# Avalon_ctrlunit.net
KiCad netlist of a schematic drawn in Altium Designer
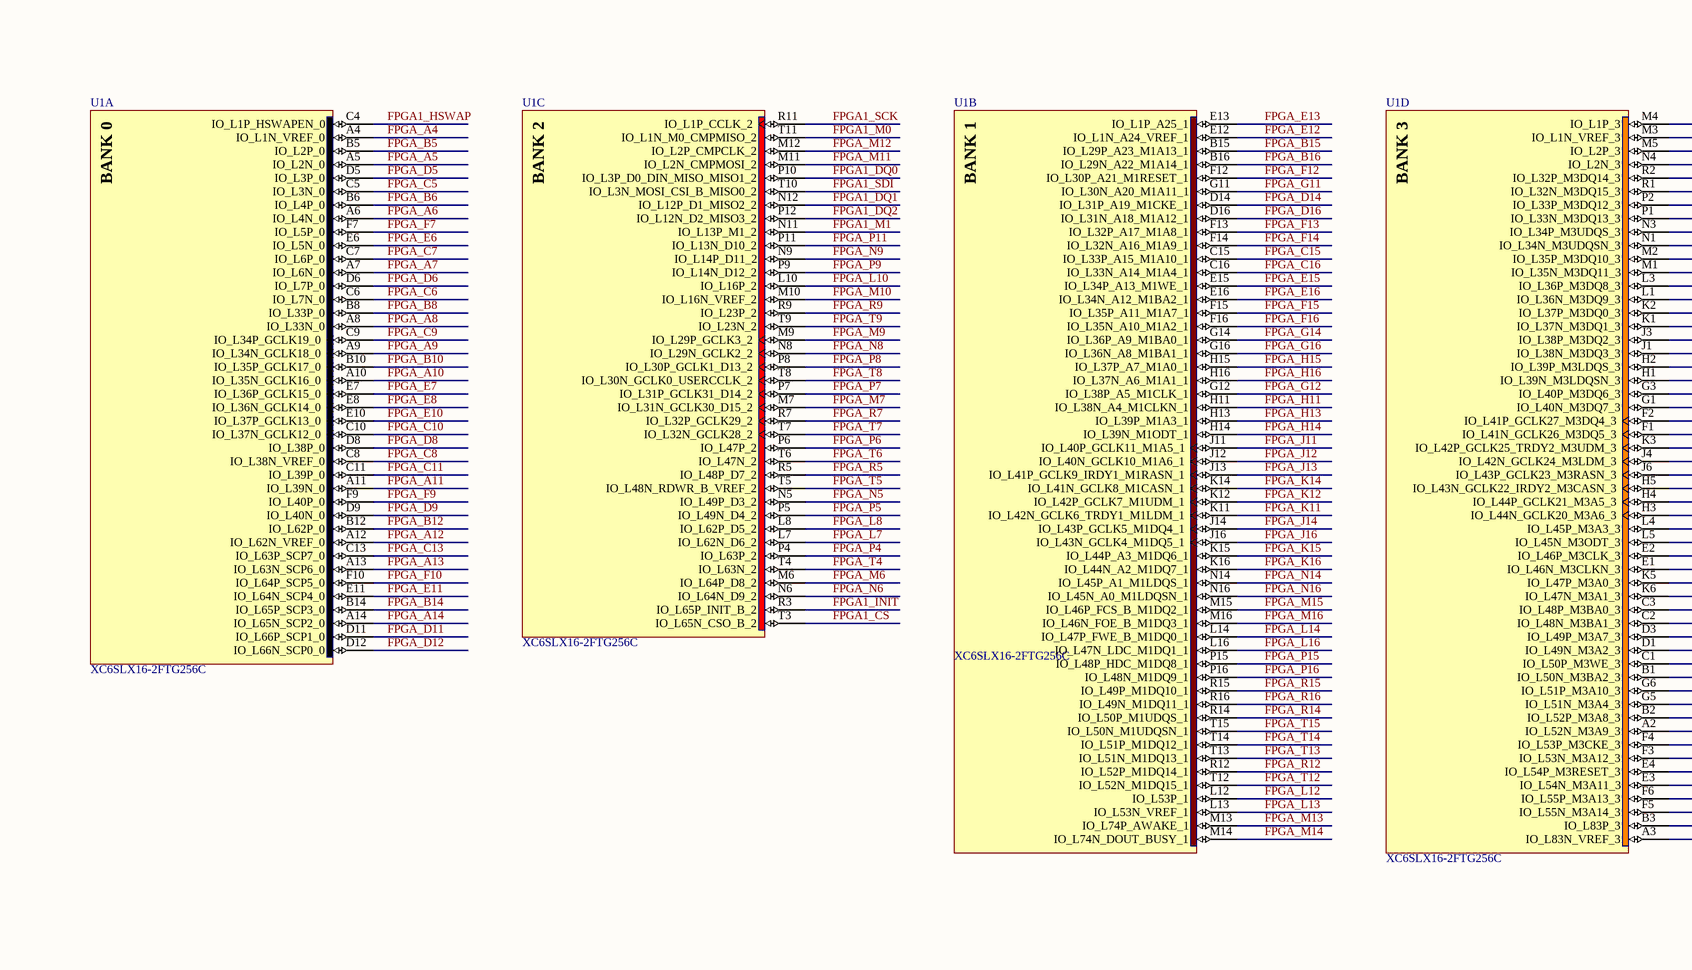
[diagram p0: Avalon_ctrlunit.SchDoc, top left]
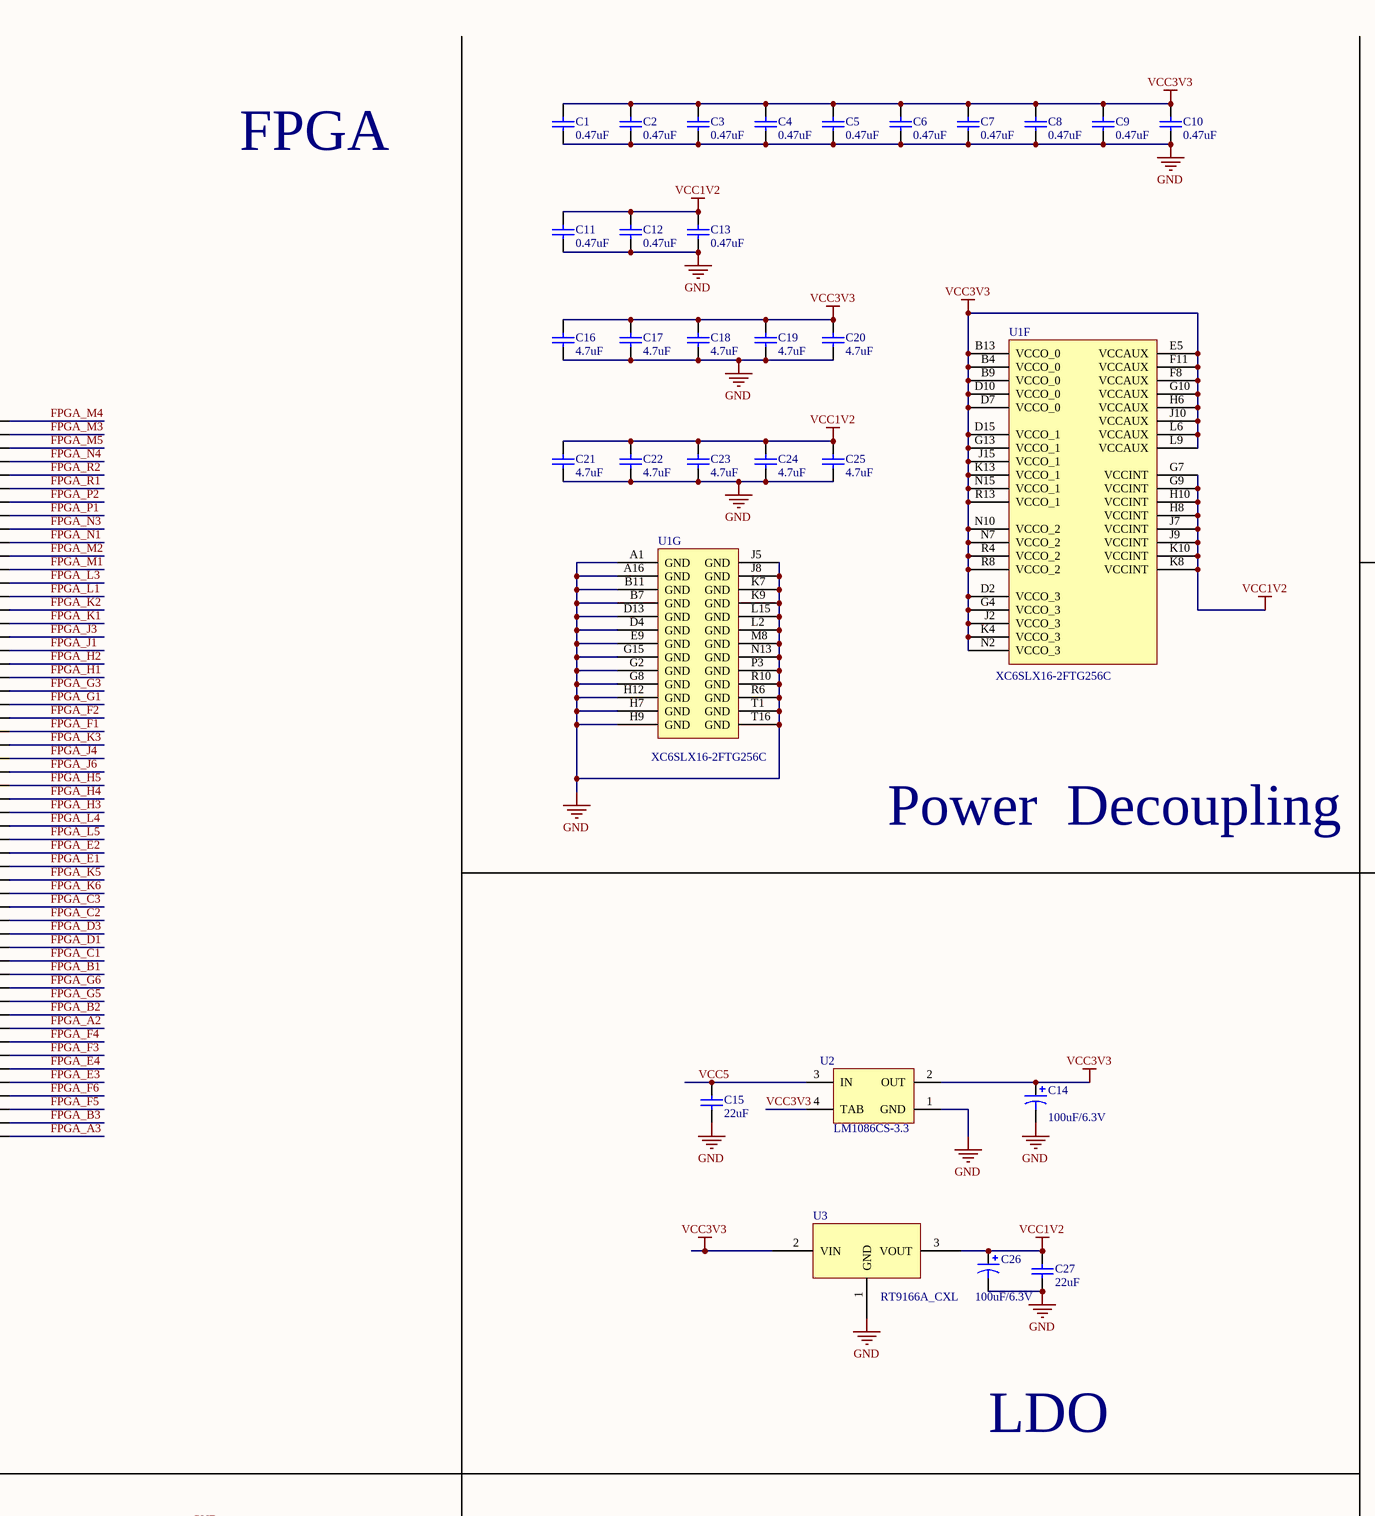
[diagram p1: Avalon_ctrlunit.SchDoc, top middle]
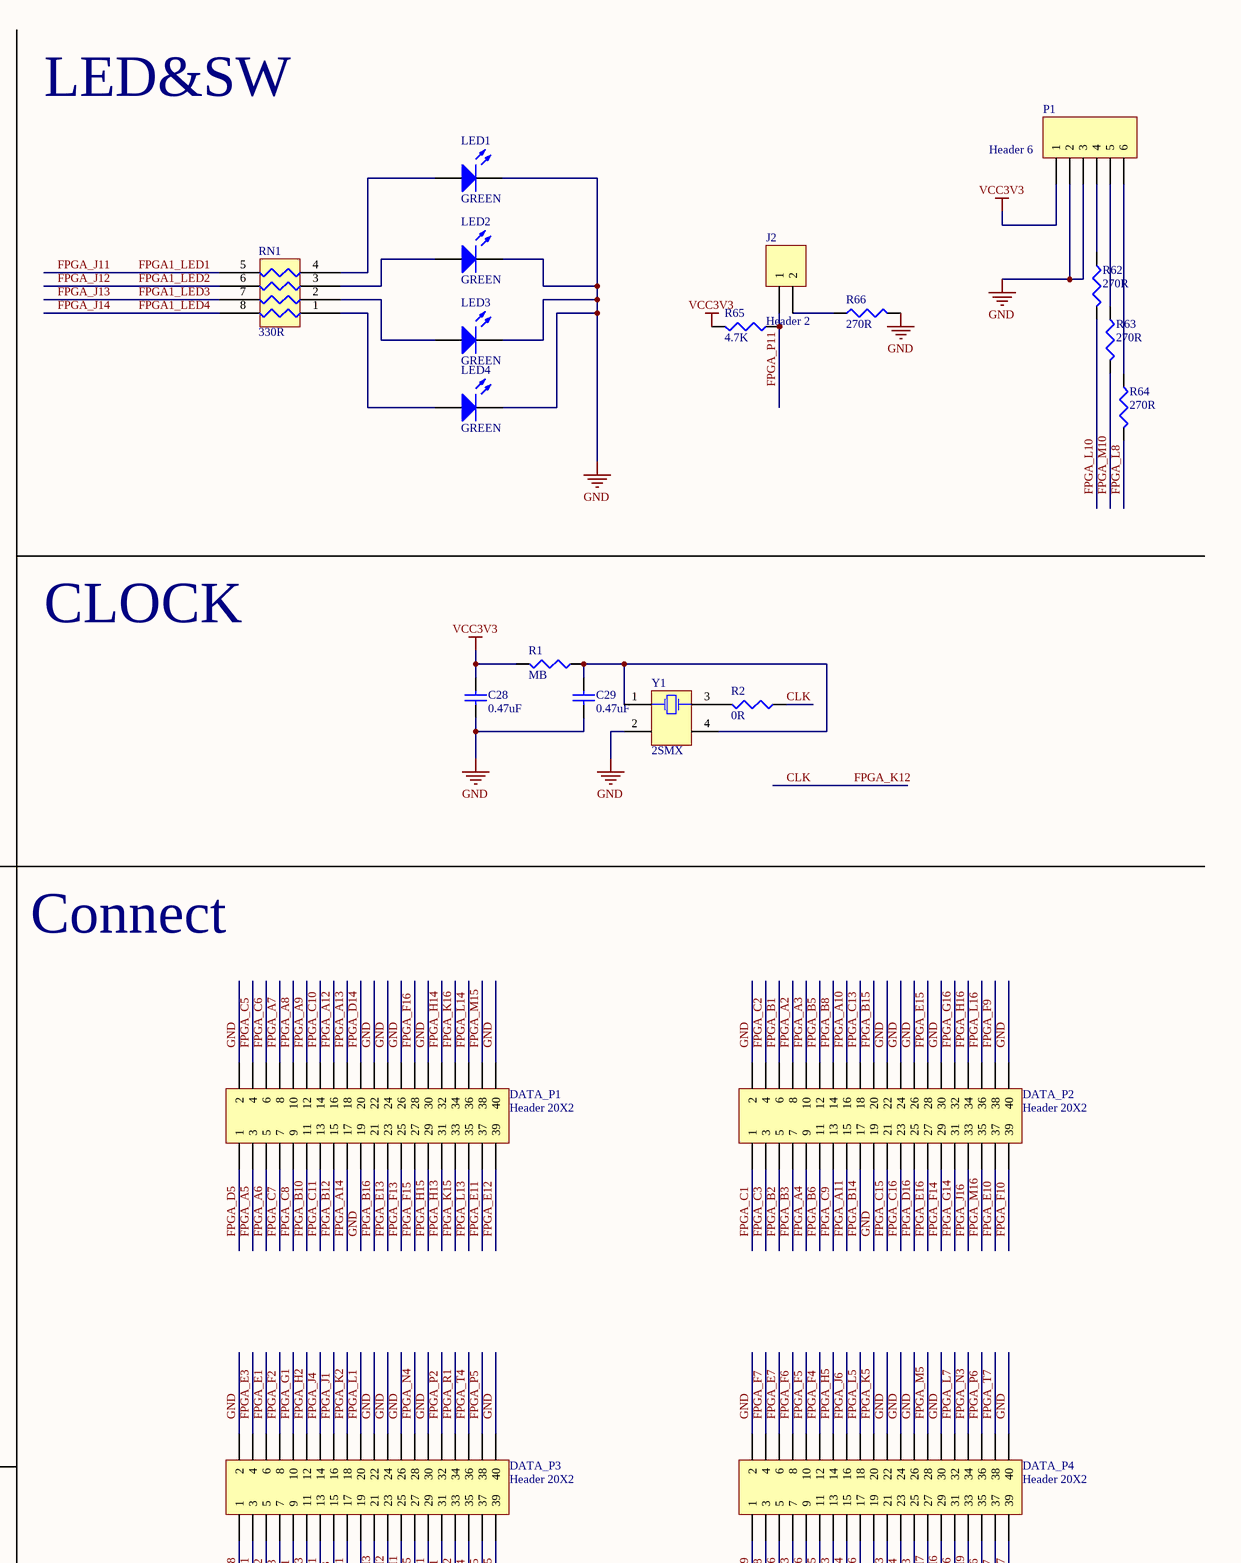
[diagram p2: Avalon_ctrlunit.SchDoc, top right]
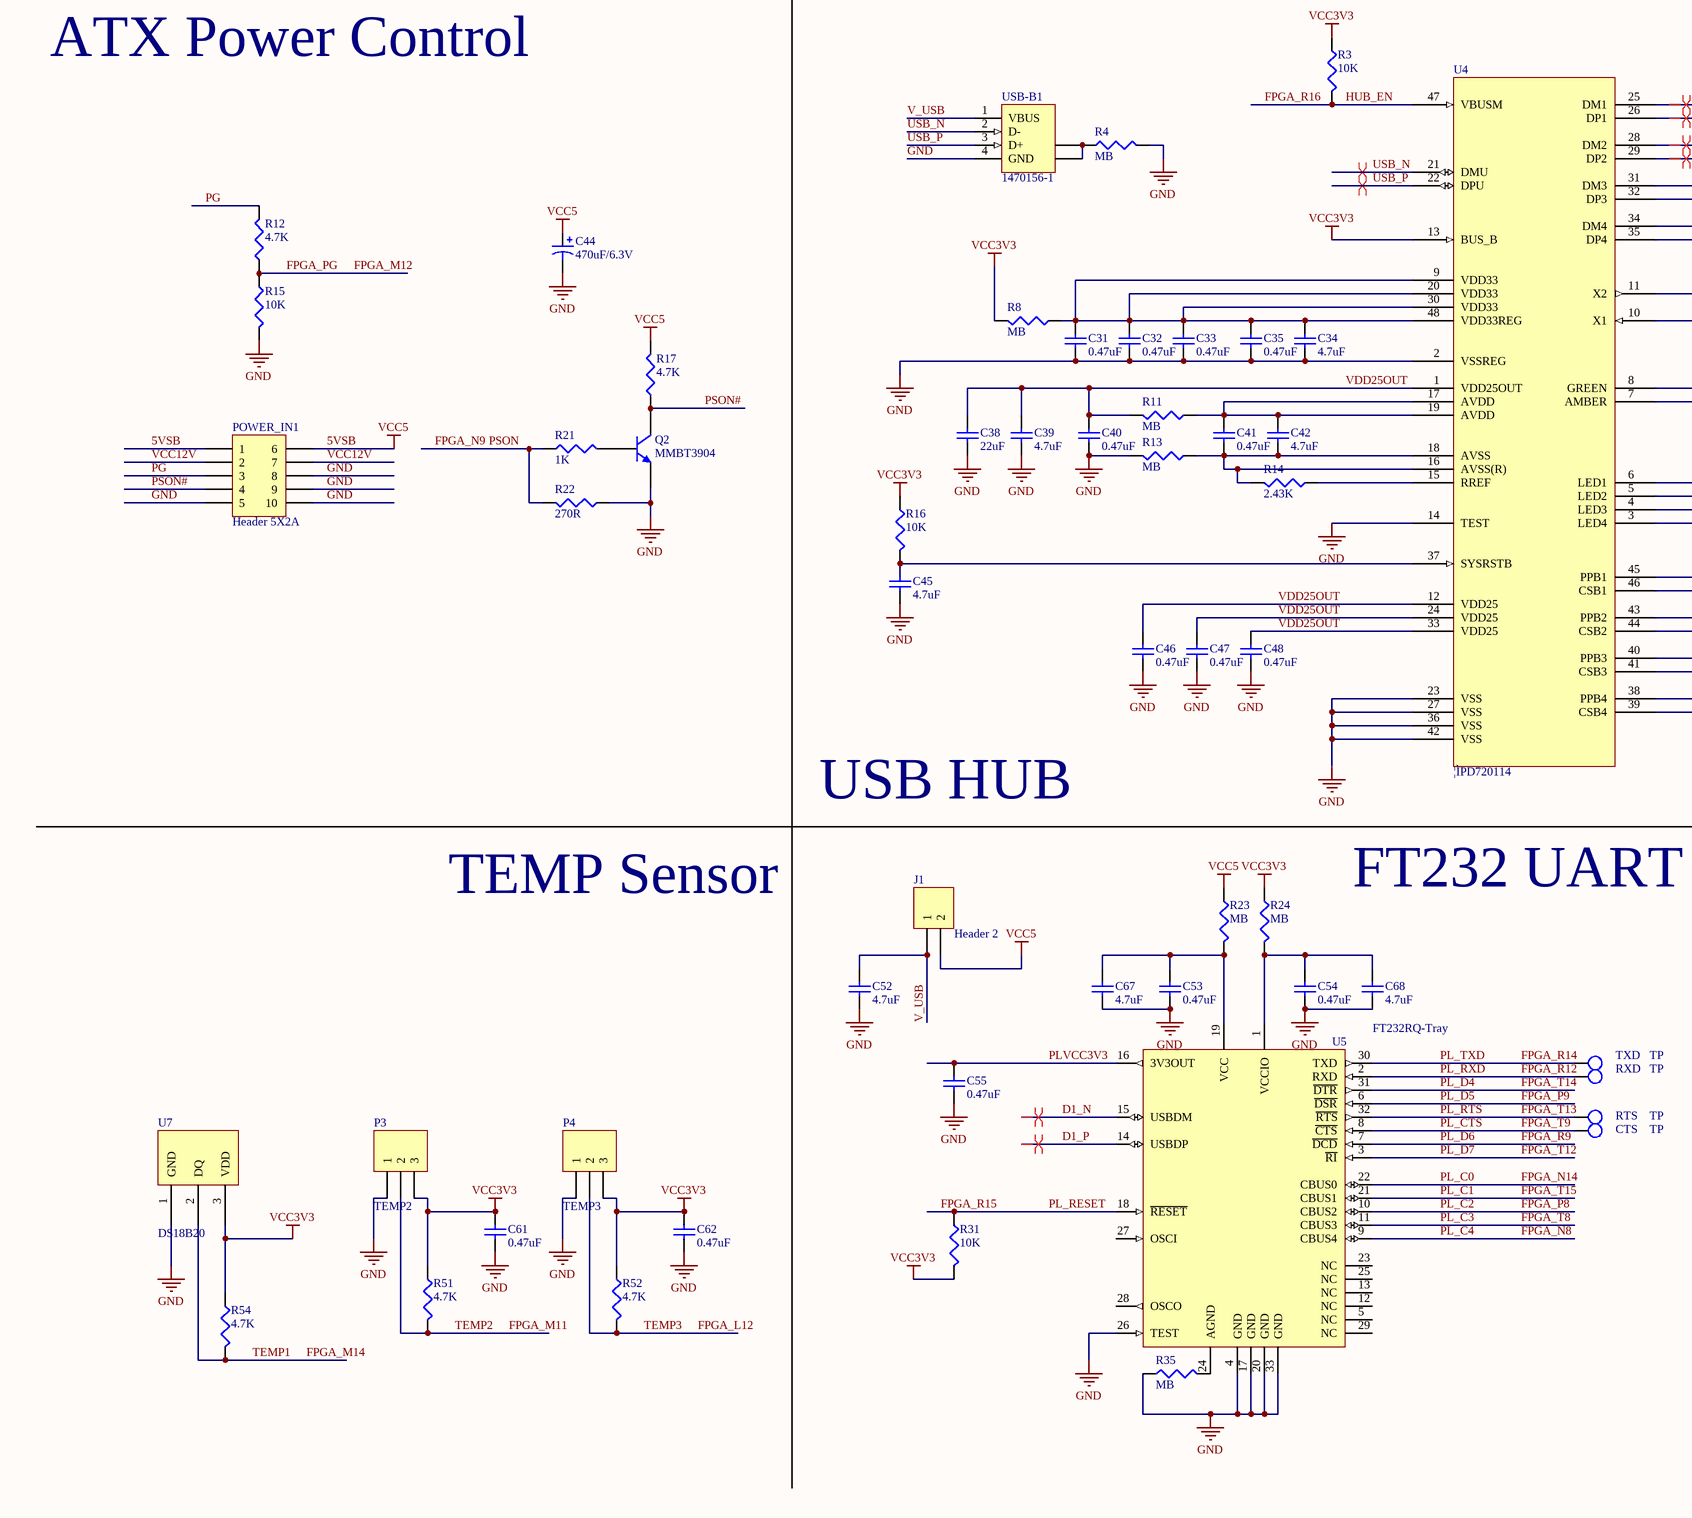
[diagram p3: Avalon_ctrlunit.SchDoc, bottom left]
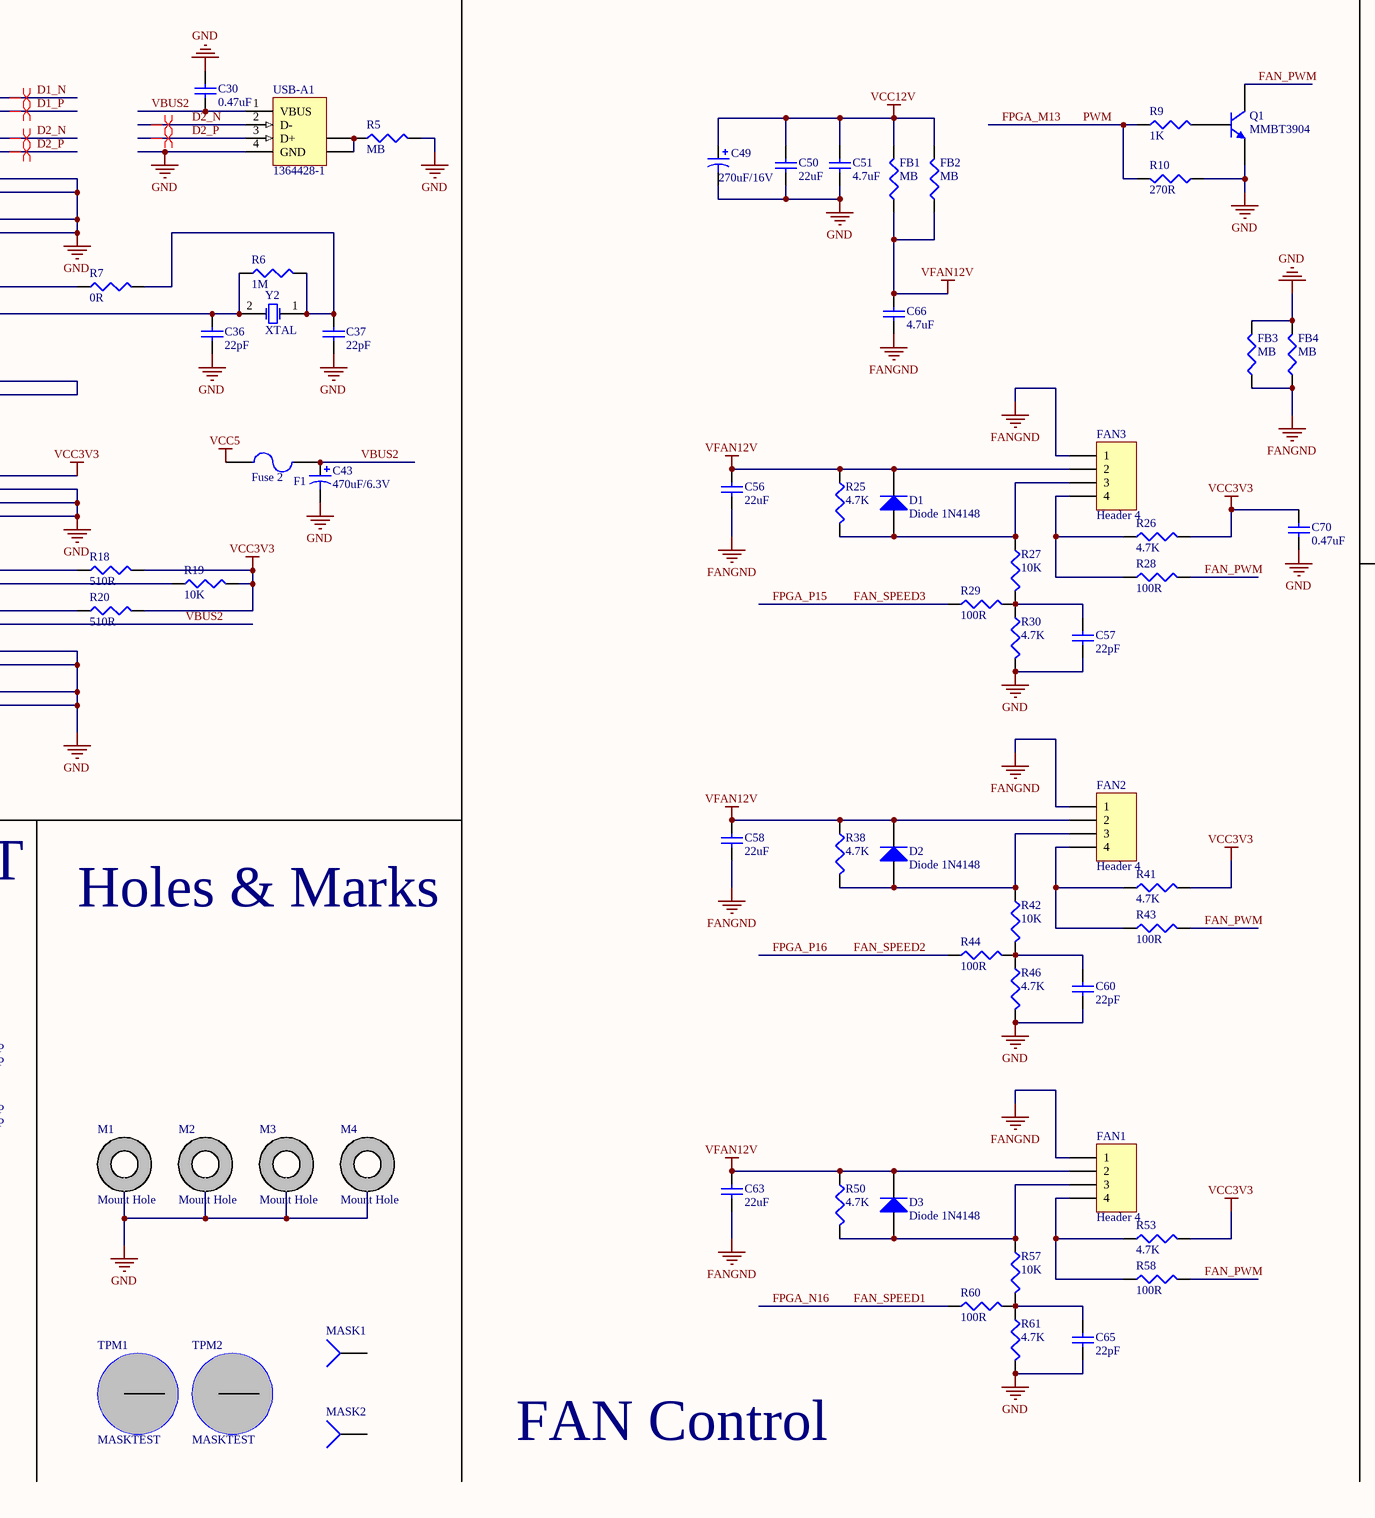
[diagram p4: Avalon_ctrlunit.SchDoc, bottom middle]
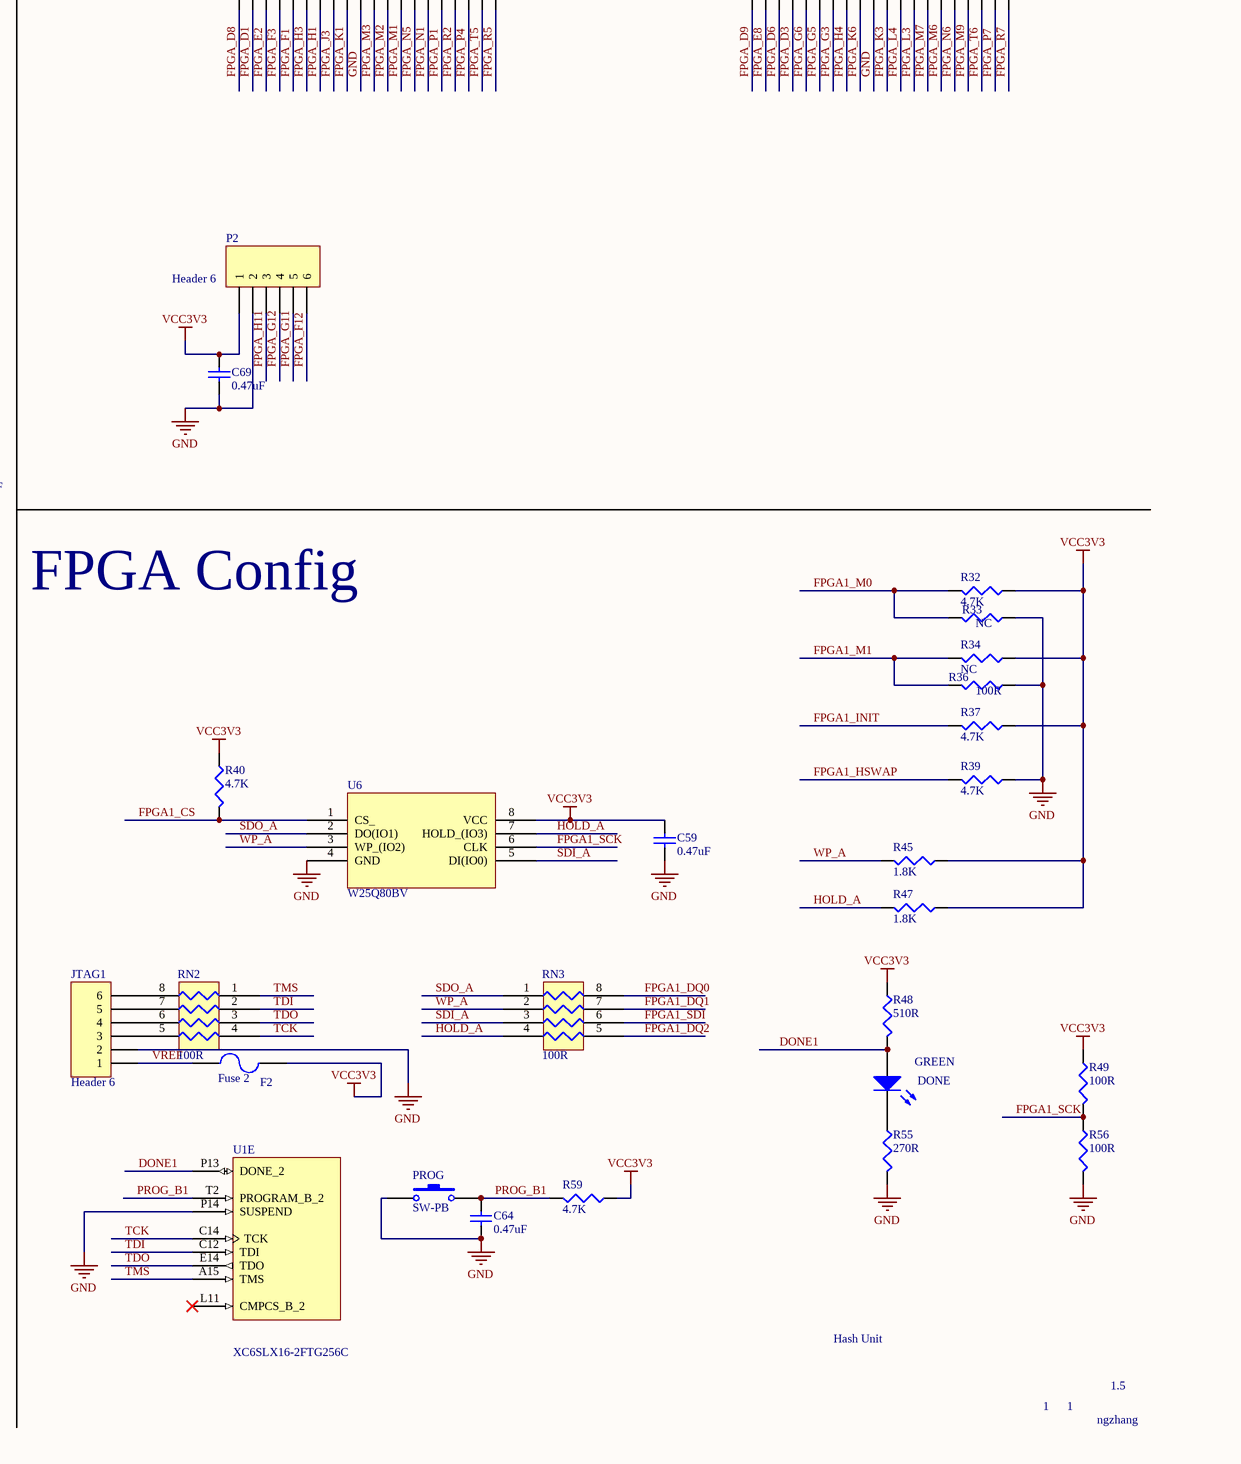
[diagram p5: Avalon_ctrlunit.SchDoc, bottom right]

(export (version "E")
  (design (tool "Eeschema 10.0.6"))
  (components
    (comp (ref "C1")
      (value "0.47uF")
      (footprint "CAPC1005L")
      (description "Capacitor (Semiconductor SIM Model)")
      (fields (field (name "PUBLISHER") "Altium Limited"))
      (libsource (lib "Miscellaneous Devices") (part "Cap Semi"))
    )
    (comp (ref "C2")
      (value "0.47uF")
      (footprint "CAPC1005L")
      (description "Capacitor (Semiconductor SIM Model)")
      (fields (field (name "PUBLISHER") "Altium Limited"))
      (libsource (lib "Miscellaneous Devices") (part "Cap Semi"))
    )
    (comp (ref "C3")
      (value "0.47uF")
      (footprint "CAPC1005L")
      (description "Capacitor (Semiconductor SIM Model)")
      (fields (field (name "PUBLISHER") "Altium Limited"))
      (libsource (lib "Miscellaneous Devices") (part "Cap Semi"))
    )
    (comp (ref "C4")
      (value "0.47uF")
      (footprint "CAPC1005L")
      (description "Capacitor (Semiconductor SIM Model)")
      (fields (field (name "PUBLISHER") "Altium Limited"))
      (libsource (lib "Miscellaneous Devices") (part "Cap Semi"))
    )
    (comp (ref "C5")
      (value "0.47uF")
      (footprint "CAPC1005L")
      (description "Capacitor (Semiconductor SIM Model)")
      (fields (field (name "PUBLISHER") "Altium Limited"))
      (libsource (lib "Miscellaneous Devices") (part "Cap Semi"))
    )
    (comp (ref "C6")
      (value "0.47uF")
      (footprint "CAPC1005L")
      (description "Capacitor (Semiconductor SIM Model)")
      (fields (field (name "PUBLISHER") "Altium Limited"))
      (libsource (lib "Miscellaneous Devices") (part "Cap Semi"))
    )
    (comp (ref "C7")
      (value "0.47uF")
      (footprint "CAPC1005L")
      (description "Capacitor (Semiconductor SIM Model)")
      (fields (field (name "PUBLISHER") "Altium Limited"))
      (libsource (lib "Miscellaneous Devices") (part "Cap Semi"))
    )
    (comp (ref "C8")
      (value "0.47uF")
      (footprint "CAPC1005L")
      (description "Capacitor (Semiconductor SIM Model)")
      (fields (field (name "PUBLISHER") "Altium Limited"))
      (libsource (lib "Miscellaneous Devices") (part "Cap Semi"))
    )
    (comp (ref "C9")
      (value "0.47uF")
      (footprint "CAPC1005L")
      (description "Capacitor (Semiconductor SIM Model)")
      (fields (field (name "PUBLISHER") "Altium Limited"))
      (libsource (lib "Miscellaneous Devices") (part "Cap Semi"))
    )
    (comp (ref "C10")
      (value "0.47uF")
      (footprint "CAPC1005L")
      (description "Capacitor (Semiconductor SIM Model)")
      (fields (field (name "PUBLISHER") "Altium Limited"))
      (libsource (lib "Miscellaneous Devices") (part "Cap Semi"))
    )
    (comp (ref "C11")
      (value "0.47uF")
      (footprint "CAPC1005L")
      (description "Capacitor (Semiconductor SIM Model)")
      (fields (field (name "PUBLISHER") "Altium Limited"))
      (libsource (lib "Miscellaneous Devices") (part "Cap Semi"))
    )
    (comp (ref "C12")
      (value "0.47uF")
      (footprint "CAPC1005L")
      (description "Capacitor (Semiconductor SIM Model)")
      (fields (field (name "PUBLISHER") "Altium Limited"))
      (libsource (lib "Miscellaneous Devices") (part "Cap Semi"))
    )
    (comp (ref "C13")
      (value "0.47uF")
      (footprint "CAPC1005L")
      (description "Capacitor (Semiconductor SIM Model)")
      (fields (field (name "PUBLISHER") "Altium Limited"))
      (libsource (lib "Miscellaneous Devices") (part "Cap Semi"))
    )
    (comp (ref "C14")
      (value "100uF/6.3V")
      (footprint "C")
      (description "Solid Tantalum Chip Capacitor, T492 Series - CWR11 Style Per Mil-PRF-55365/8")
      (fields (field (name "PUBLISHER") "Altium Limited"))
      (libsource (lib "KEMET Chip Capacitor") (part "T492C"))
    )
    (comp (ref "C15")
      (value "22uF")
      (footprint "CAPC3216L")
      (description "Capacitor (Semiconductor SIM Model)")
      (fields (field (name "PUBLISHER") "Altium Limited"))
      (libsource (lib "Miscellaneous Devices") (part "Cap Semi"))
    )
    (comp (ref "C16")
      (value "4.7uF")
      (footprint "CAPC1608L")
      (description "Capacitor (Semiconductor SIM Model)")
      (fields (field (name "PUBLISHER") "Altium Limited"))
      (libsource (lib "Miscellaneous Devices") (part "Cap Semi"))
    )
    (comp (ref "C17")
      (value "4.7uF")
      (footprint "CAPC1608L")
      (description "Capacitor (Semiconductor SIM Model)")
      (fields (field (name "PUBLISHER") "Altium Limited"))
      (libsource (lib "Miscellaneous Devices") (part "Cap Semi"))
    )
    (comp (ref "C18")
      (value "4.7uF")
      (footprint "CAPC1608L")
      (description "Capacitor (Semiconductor SIM Model)")
      (fields (field (name "PUBLISHER") "Altium Limited"))
      (libsource (lib "Miscellaneous Devices") (part "Cap Semi"))
    )
    (comp (ref "C19")
      (value "4.7uF")
      (footprint "CAPC1608L")
      (description "Capacitor (Semiconductor SIM Model)")
      (fields (field (name "PUBLISHER") "Altium Limited"))
      (libsource (lib "Miscellaneous Devices") (part "Cap Semi"))
    )
    (comp (ref "C20")
      (value "4.7uF")
      (footprint "CAPC1608L")
      (description "Capacitor (Semiconductor SIM Model)")
      (fields (field (name "PUBLISHER") "Altium Limited"))
      (libsource (lib "Miscellaneous Devices") (part "Cap Semi"))
    )
    (comp (ref "C21")
      (value "4.7uF")
      (footprint "CAPC1608L")
      (description "Capacitor (Semiconductor SIM Model)")
      (fields (field (name "PUBLISHER") "Altium Limited"))
      (libsource (lib "Miscellaneous Devices") (part "Cap Semi"))
    )
    (comp (ref "C22")
      (value "4.7uF")
      (footprint "CAPC1608L")
      (description "Capacitor (Semiconductor SIM Model)")
      (fields (field (name "PUBLISHER") "Altium Limited"))
      (libsource (lib "Miscellaneous Devices") (part "Cap Semi"))
    )
    (comp (ref "C23")
      (value "4.7uF")
      (footprint "CAPC1608L")
      (description "Capacitor (Semiconductor SIM Model)")
      (fields (field (name "PUBLISHER") "Altium Limited"))
      (libsource (lib "Miscellaneous Devices") (part "Cap Semi"))
    )
    (comp (ref "C24")
      (value "4.7uF")
      (footprint "CAPC1608L")
      (description "Capacitor (Semiconductor SIM Model)")
      (fields (field (name "PUBLISHER") "Altium Limited"))
      (libsource (lib "Miscellaneous Devices") (part "Cap Semi"))
    )
    (comp (ref "C25")
      (value "4.7uF")
      (footprint "CAPC1608L")
      (description "Capacitor (Semiconductor SIM Model)")
      (fields (field (name "PUBLISHER") "Altium Limited"))
      (libsource (lib "Miscellaneous Devices") (part "Cap Semi"))
    )
    (comp (ref "C26")
      (value "100uF/6.3V")
      (footprint "C")
      (description "Solid Tantalum Chip Capacitor, T492 Series - CWR11 Style Per Mil-PRF-55365/8")
      (fields (field (name "PUBLISHER") "Altium Limited"))
      (libsource (lib "KEMET Chip Capacitor") (part "T492C"))
    )
    (comp (ref "C27")
      (value "22uF")
      (footprint "CAPC3216L")
      (description "Capacitor (Semiconductor SIM Model)")
      (fields (field (name "PUBLISHER") "Altium Limited"))
      (libsource (lib "Miscellaneous Devices") (part "Cap Semi"))
    )
    (comp (ref "C28")
      (value "0.47uF")
      (footprint "CAPC1005L")
      (description "Capacitor (Semiconductor SIM Model)")
      (fields (field (name "PUBLISHER") "Altium Limited"))
      (libsource (lib "Miscellaneous Devices") (part "Cap Semi"))
    )
    (comp (ref "C29")
      (value "0.47uF")
      (footprint "CAPC1005L")
      (description "Capacitor (Semiconductor SIM Model)")
      (fields (field (name "PUBLISHER") "Altium Limited"))
      (libsource (lib "Miscellaneous Devices") (part "Cap Semi"))
    )
    (comp (ref "C30")
      (value "0.47uF")
      (footprint "CAPC1005L")
      (description "Capacitor (Semiconductor SIM Model)")
      (fields (field (name "PUBLISHER") "Altium Limited"))
      (libsource (lib "Miscellaneous Devices") (part "Cap Semi"))
    )
    (comp (ref "C31")
      (value "0.47uF")
      (footprint "CAPC1005L")
      (description "Capacitor (Semiconductor SIM Model)")
      (fields (field (name "PUBLISHER") "Altium Limited"))
      (libsource (lib "Miscellaneous Devices") (part "Cap Semi"))
    )
    (comp (ref "C32")
      (value "0.47uF")
      (footprint "CAPC1005L")
      (description "Capacitor (Semiconductor SIM Model)")
      (fields (field (name "PUBLISHER") "Altium Limited"))
      (libsource (lib "Miscellaneous Devices") (part "Cap Semi"))
    )
    (comp (ref "C33")
      (value "0.47uF")
      (footprint "CAPC1005L")
      (description "Capacitor (Semiconductor SIM Model)")
      (fields (field (name "PUBLISHER") "Altium Limited"))
      (libsource (lib "Miscellaneous Devices") (part "Cap Semi"))
    )
    (comp (ref "C34")
      (value "4.7uF")
      (footprint "CAPC1608L")
      (description "Capacitor (Semiconductor SIM Model)")
      (fields (field (name "PUBLISHER") "Altium Limited"))
      (libsource (lib "Miscellaneous Devices") (part "Cap Semi"))
    )
    (comp (ref "C35")
      (value "0.47uF")
      (footprint "CAPC1005L")
      (description "Capacitor (Semiconductor SIM Model)")
      (fields (field (name "PUBLISHER") "Altium Limited"))
      (libsource (lib "Miscellaneous Devices") (part "Cap Semi"))
    )
    (comp (ref "C36")
      (value "22pF")
      (footprint "CAPC1005L")
      (description "Capacitor (Semiconductor SIM Model)")
      (fields (field (name "PUBLISHER") "Altium Limited"))
      (libsource (lib "Miscellaneous Devices") (part "Cap Semi"))
    )
    (comp (ref "C37")
      (value "22pF")
      (footprint "CAPC1005L")
      (description "Capacitor (Semiconductor SIM Model)")
      (fields (field (name "PUBLISHER") "Altium Limited"))
      (libsource (lib "Miscellaneous Devices") (part "Cap Semi"))
    )
    (comp (ref "C38")
      (value "22uF")
      (footprint "CAPC3216L")
      (description "Capacitor (Semiconductor SIM Model)")
      (fields (field (name "PUBLISHER") "Altium Limited"))
      (libsource (lib "Miscellaneous Devices") (part "Cap Semi"))
    )
    (comp (ref "C39")
      (value "4.7uF")
      (footprint "CAPC1608L")
      (description "Capacitor (Semiconductor SIM Model)")
      (fields (field (name "PUBLISHER") "Altium Limited"))
      (libsource (lib "Miscellaneous Devices") (part "Cap Semi"))
    )
    (comp (ref "C40")
      (value "0.47uF")
      (footprint "CAPC1005L")
      (description "Capacitor (Semiconductor SIM Model)")
      (fields (field (name "PUBLISHER") "Altium Limited"))
      (libsource (lib "Miscellaneous Devices") (part "Cap Semi"))
    )
    (comp (ref "C41")
      (value "0.47uF")
      (footprint "CAPC1005L")
      (description "Capacitor (Semiconductor SIM Model)")
      (fields (field (name "PUBLISHER") "Altium Limited"))
      (libsource (lib "Miscellaneous Devices") (part "Cap Semi"))
    )
    (comp (ref "C42")
      (value "4.7uF")
      (footprint "CAPC1608L")
      (description "Capacitor (Semiconductor SIM Model)")
      (fields (field (name "PUBLISHER") "Altium Limited"))
      (libsource (lib "Miscellaneous Devices") (part "Cap Semi"))
    )
    (comp (ref "C43")
      (value "470uF/6.3V")
      (footprint "CAP8X8")
      (description "Polarized Capacitor (Radial)")
      (fields (field (name "PUBLISHER") "Altium Limited"))
      (libsource (lib "S6_2") (part "Cap Pol1"))
    )
    (comp (ref "C44")
      (value "470uF/6.3V")
      (footprint "CAP8X8")
      (description "Polarized Capacitor (Radial)")
      (fields (field (name "PUBLISHER") "Altium Limited"))
      (libsource (lib "S6_2") (part "Cap Pol1"))
    )
    (comp (ref "C45")
      (value "4.7uF")
      (footprint "CAPC1608L")
      (description "Capacitor (Semiconductor SIM Model)")
      (fields (field (name "PUBLISHER") "Altium Limited"))
      (libsource (lib "Miscellaneous Devices") (part "Cap Semi"))
    )
    (comp (ref "C46")
      (value "0.47uF")
      (footprint "CAPC1005L")
      (description "Capacitor (Semiconductor SIM Model)")
      (fields (field (name "PUBLISHER") "Altium Limited"))
      (libsource (lib "Miscellaneous Devices") (part "Cap Semi"))
    )
    (comp (ref "C47")
      (value "0.47uF")
      (footprint "CAPC1005L")
      (description "Capacitor (Semiconductor SIM Model)")
      (fields (field (name "PUBLISHER") "Altium Limited"))
      (libsource (lib "Miscellaneous Devices") (part "Cap Semi"))
    )
    (comp (ref "C48")
      (value "0.47uF")
      (footprint "CAPC1005L")
      (description "Capacitor (Semiconductor SIM Model)")
      (fields (field (name "PUBLISHER") "Altium Limited"))
      (libsource (lib "Miscellaneous Devices") (part "Cap Semi"))
    )
    (comp (ref "C49")
      (value "270uF/16V")
      (footprint "CAP8X8")
      (description "Polarized Capacitor (Radial)")
      (fields (field (name "PUBLISHER") "Altium Limited"))
      (libsource (lib "S6_2") (part "Cap Pol1"))
    )
    (comp (ref "C50")
      (value "22uF")
      (footprint "CAPC3225N")
      (description "Capacitor (Semiconductor SIM Model)")
      (fields (field (name "PUBLISHER") "Altium Limited"))
      (libsource (lib "Miscellaneous Devices") (part "Cap Semi"))
    )
    (comp (ref "C51")
      (value "4.7uF")
      (footprint "CAPC1608L")
      (description "Capacitor (Semiconductor SIM Model)")
      (fields (field (name "PUBLISHER") "Altium Limited"))
      (libsource (lib "Miscellaneous Devices") (part "Cap Semi"))
    )
    (comp (ref "C52")
      (value "4.7uF")
      (footprint "CAPC1608L")
      (description "Capacitor (Semiconductor SIM Model)")
      (fields (field (name "PUBLISHER") "Altium Limited"))
      (libsource (lib "Miscellaneous Devices") (part "Cap Semi"))
    )
    (comp (ref "C53")
      (value "0.47uF")
      (footprint "CAPC1005L")
      (description "Capacitor (Semiconductor SIM Model)")
      (fields (field (name "PUBLISHER") "Altium Limited"))
      (libsource (lib "Miscellaneous Devices") (part "Cap Semi"))
    )
    (comp (ref "C54")
      (value "0.47uF")
      (footprint "CAPC1005L")
      (description "Capacitor (Semiconductor SIM Model)")
      (fields (field (name "PUBLISHER") "Altium Limited"))
      (libsource (lib "Miscellaneous Devices") (part "Cap Semi"))
    )
    (comp (ref "C55")
      (value "0.47uF")
      (footprint "CAPC1005L")
      (description "Capacitor (Semiconductor SIM Model)")
      (fields (field (name "PUBLISHER") "Altium Limited"))
      (libsource (lib "Miscellaneous Devices") (part "Cap Semi"))
    )
    (comp (ref "C56")
      (value "22uF")
      (footprint "CAPC3225N")
      (description "Capacitor (Semiconductor SIM Model)")
      (fields (field (name "PUBLISHER") "Altium Limited"))
      (libsource (lib "Miscellaneous Devices") (part "Cap Semi"))
    )
    (comp (ref "C57")
      (value "22pF")
      (footprint "CAPC1005L")
      (description "Capacitor (Semiconductor SIM Model)")
      (fields (field (name "PUBLISHER") "Altium Limited"))
      (libsource (lib "Miscellaneous Devices") (part "Cap Semi"))
    )
    (comp (ref "C58")
      (value "22uF")
      (footprint "CAPC3225N")
      (description "Capacitor (Semiconductor SIM Model)")
      (fields (field (name "PUBLISHER") "Altium Limited"))
      (libsource (lib "Miscellaneous Devices") (part "Cap Semi"))
    )
    (comp (ref "C59")
      (value "0.47uF")
      (footprint "CAPC1005L")
      (description "Capacitor (Semiconductor SIM Model)")
      (fields (field (name "PUBLISHER") "Altium Limited"))
      (libsource (lib "Miscellaneous Devices") (part "Cap Semi"))
    )
    (comp (ref "C60")
      (value "22pF")
      (footprint "CAPC1005L")
      (description "Capacitor (Semiconductor SIM Model)")
      (fields (field (name "PUBLISHER") "Altium Limited"))
      (libsource (lib "Miscellaneous Devices") (part "Cap Semi"))
    )
    (comp (ref "C61")
      (value "0.47uF")
      (footprint "CAPC1005L")
      (description "Capacitor (Semiconductor SIM Model)")
      (fields (field (name "PUBLISHER") "Altium Limited"))
      (libsource (lib "Miscellaneous Devices") (part "Cap Semi"))
    )
    (comp (ref "C62")
      (value "0.47uF")
      (footprint "CAPC1005L")
      (description "Capacitor (Semiconductor SIM Model)")
      (fields (field (name "PUBLISHER") "Altium Limited"))
      (libsource (lib "Miscellaneous Devices") (part "Cap Semi"))
    )
    (comp (ref "C63")
      (value "22uF")
      (footprint "CAPC3225N")
      (description "Capacitor (Semiconductor SIM Model)")
      (fields (field (name "PUBLISHER") "Altium Limited"))
      (libsource (lib "Miscellaneous Devices") (part "Cap Semi"))
    )
    (comp (ref "C64")
      (value "0.47uF")
      (footprint "CAPC1005L")
      (description "Capacitor (Semiconductor SIM Model)")
      (fields (field (name "PUBLISHER") "Altium Limited"))
      (libsource (lib "Miscellaneous Devices") (part "Cap Semi"))
    )
    (comp (ref "C65")
      (value "22pF")
      (footprint "CAPC1005L")
      (description "Capacitor (Semiconductor SIM Model)")
      (fields (field (name "PUBLISHER") "Altium Limited"))
      (libsource (lib "Miscellaneous Devices") (part "Cap Semi"))
    )
    (comp (ref "C66")
      (value "4.7uF")
      (footprint "CAPC1608L")
      (description "Capacitor (Semiconductor SIM Model)")
      (fields (field (name "PUBLISHER") "Altium Limited"))
      (libsource (lib "Miscellaneous Devices") (part "Cap Semi"))
    )
    (comp (ref "C67")
      (value "4.7uF")
      (footprint "CAPC1608L")
      (description "Capacitor (Semiconductor SIM Model)")
      (fields (field (name "PUBLISHER") "Altium Limited"))
      (libsource (lib "Miscellaneous Devices") (part "Cap Semi"))
    )
    (comp (ref "C68")
      (value "4.7uF")
      (footprint "CAPC1608L")
      (description "Capacitor (Semiconductor SIM Model)")
      (fields (field (name "PUBLISHER") "Altium Limited"))
      (libsource (lib "Miscellaneous Devices") (part "Cap Semi"))
    )
    (comp (ref "C69")
      (value "0.47uF")
      (footprint "CAPC1005L")
      (description "Capacitor (Semiconductor SIM Model)")
      (fields (field (name "PUBLISHER") "Altium Limited"))
      (libsource (lib "Miscellaneous Devices") (part "Cap Semi"))
    )
    (comp (ref "C70")
      (value "0.47uF")
      (footprint "CAPC1005L")
      (description "Capacitor (Semiconductor SIM Model)")
      (fields (field (name "PUBLISHER") "Altium Limited"))
      (libsource (lib "Miscellaneous Devices") (part "Cap Semi"))
    )
    (comp (ref "CTS") (value "TP") (footprint "TP") (libsource (lib "S6") (part "TP")))
    (comp (ref "D1")
      (value "Diode 1N4148")
      (footprint "CD3216-1206")
      (description "High Conductance Fast Diode")
      (fields (field (name "PUBLISHER") "Altium Limited"))
      (libsource (lib "Miscellaneous Devices") (part "Diode 1N4148"))
    )
    (comp (ref "D2")
      (value "Diode 1N4148")
      (footprint "CD3216-1206")
      (description "High Conductance Fast Diode")
      (fields (field (name "PUBLISHER") "Altium Limited"))
      (libsource (lib "Miscellaneous Devices") (part "Diode 1N4148"))
    )
    (comp (ref "D3")
      (value "Diode 1N4148")
      (footprint "CD3216-1206")
      (description "High Conductance Fast Diode")
      (fields (field (name "PUBLISHER") "Altium Limited"))
      (libsource (lib "Miscellaneous Devices") (part "Diode 1N4148"))
    )
    (comp (ref "DATA_P1")
      (value "Header 20X2")
      (footprint "IDE40")
      (description "Header, 20-Pin, Dual row")
      (fields (field (name "PUBLISHER") "Altium Limited"))
      (libsource (lib "Miscellaneous Connectors") (part "Header 20X2"))
    )
    (comp (ref "DATA_P2")
      (value "Header 20X2")
      (footprint "IDE40")
      (description "Header, 20-Pin, Dual row")
      (fields (field (name "PUBLISHER") "Altium Limited"))
      (libsource (lib "Miscellaneous Connectors") (part "Header 20X2"))
    )
    (comp (ref "DATA_P3")
      (value "Header 20X2")
      (footprint "IDE40")
      (description "Header, 20-Pin, Dual row")
      (fields (field (name "PUBLISHER") "Altium Limited"))
      (libsource (lib "Miscellaneous Connectors") (part "Header 20X2"))
    )
    (comp (ref "DATA_P4")
      (value "Header 20X2")
      (footprint "IDE40")
      (description "Header, 20-Pin, Dual row")
      (fields (field (name "PUBLISHER") "Altium Limited"))
      (libsource (lib "Miscellaneous Connectors") (part "Header 20X2"))
    )
    (comp (ref "DONE")
      (value "GREEN")
      (footprint "CD1608-0603")
      (description "Typical BLUE SiC LED")
      (fields (field (name "PUBLISHER") "Altium Limited"))
      (libsource (lib "Miscellaneous Devices") (part "LED3"))
    )
    (comp (ref "F1")
      (value "Fuse 2")
      (footprint "RESC3216N")
      (description "Fuse")
      (fields (field (name "PUBLISHER") "Altium Limited"))
      (libsource (lib "Miscellaneous Devices") (part "Fuse 2"))
    )
    (comp (ref "F2")
      (value "Fuse 2")
      (footprint "RESC3216N")
      (description "Fuse")
      (fields (field (name "PUBLISHER") "Altium Limited"))
      (libsource (lib "Miscellaneous Devices") (part "Fuse 2"))
    )
    (comp (ref "FAN1")
      (value "Header 4")
      (footprint "4PINFAN")
      (description "Header, 4-Pin")
      (fields (field (name "PUBLISHER") "Altium Limited"))
      (libsource (lib "Miscellaneous Connectors") (part "Header 4"))
    )
    (comp (ref "FAN2")
      (value "Header 4")
      (footprint "4PINFAN")
      (description "Header, 4-Pin")
      (fields (field (name "PUBLISHER") "Altium Limited"))
      (libsource (lib "Miscellaneous Connectors") (part "Header 4"))
    )
    (comp (ref "FAN3")
      (value "Header 4")
      (footprint "4PINFAN")
      (description "Header, 4-Pin")
      (fields (field (name "PUBLISHER") "Altium Limited"))
      (libsource (lib "Miscellaneous Connectors") (part "Header 4"))
    )
    (comp (ref "FB1")
      (value "MB")
      (footprint "INDC3216L")
      (description "Resistor")
      (fields (field (name "PUBLISHER") "Altium Limited"))
      (libsource (lib "Miscellaneous Devices") (part "Res3"))
    )
    (comp (ref "FB2")
      (value "MB")
      (footprint "INDC3216L")
      (description "Resistor")
      (fields (field (name "PUBLISHER") "Altium Limited"))
      (libsource (lib "Miscellaneous Devices") (part "Res3"))
    )
    (comp (ref "FB3")
      (value "MB")
      (footprint "INDC3216L")
      (description "Resistor")
      (fields (field (name "PUBLISHER") "Altium Limited"))
      (libsource (lib "Miscellaneous Devices") (part "Res3"))
    )
    (comp (ref "FB4")
      (value "MB")
      (footprint "INDC3216L")
      (description "Resistor")
      (fields (field (name "PUBLISHER") "Altium Limited"))
      (libsource (lib "Miscellaneous Devices") (part "Res3"))
    )
    (comp (ref "J1")
      (value "Header 2")
      (footprint "HDR1X2")
      (description "Header, 2-Pin")
      (fields (field (name "PUBLISHER") "Altium Limited"))
      (libsource (lib "Miscellaneous Connectors") (part "Header 2"))
    )
    (comp (ref "J2")
      (value "Header 2")
      (footprint "HDR1X2")
      (description "Header, 2-Pin")
      (fields (field (name "PUBLISHER") "Altium Limited"))
      (libsource (lib "Miscellaneous Connectors") (part "Header 2"))
    )
    (comp (ref "JTAG1")
      (value "Header 6")
      (footprint "HDR1X6")
      (description "Header, 6-Pin")
      (fields (field (name "PUBLISHER") "Altium Limited"))
      (libsource (lib "Miscellaneous Connectors") (part "Header 6"))
    )
    (comp (ref "LED1")
      (value "GREEN")
      (footprint "CD1608-0603")
      (description "Typical BLUE SiC LED")
      (fields (field (name "PUBLISHER") "Altium Limited"))
      (libsource (lib "Miscellaneous Devices") (part "LED3"))
    )
    (comp (ref "LED2")
      (value "GREEN")
      (footprint "CD1608-0603")
      (description "Typical BLUE SiC LED")
      (fields (field (name "PUBLISHER") "Altium Limited"))
      (libsource (lib "Miscellaneous Devices") (part "LED3"))
    )
    (comp (ref "LED3")
      (value "GREEN")
      (footprint "CD1608-0603")
      (description "Typical BLUE SiC LED")
      (fields (field (name "PUBLISHER") "Altium Limited"))
      (libsource (lib "Miscellaneous Devices") (part "LED3"))
    )
    (comp (ref "LED4")
      (value "GREEN")
      (footprint "CD1608-0603")
      (description "Typical BLUE SiC LED")
      (fields (field (name "PUBLISHER") "Altium Limited"))
      (libsource (lib "Miscellaneous Devices") (part "LED3"))
    )
    (comp (ref "M1") (value "Mount Hole") (footprint "MHOLE2") (libsource (lib "S6_2") (part "M_Hole")))
    (comp (ref "M2") (value "Mount Hole") (footprint "MHOLE2") (libsource (lib "S6_2") (part "M_Hole")))
    (comp (ref "M3") (value "Mount Hole") (footprint "MHOLE2") (libsource (lib "S6_2") (part "M_Hole")))
    (comp (ref "M4") (value "Mount Hole") (footprint "MHOLE2") (libsource (lib "S6_2") (part "M_Hole")))
    (comp (ref "MASK1")
      (value "Socket")
      (footprint "MASK_LT")
      (fields (field (name "PUBLISHER") "Altium Limited"))
      (libsource (lib "Miscellaneous Connectors") (part "Socket"))
    )
    (comp (ref "MASK2")
      (value "Socket")
      (footprint "MASK_LT")
      (fields (field (name "PUBLISHER") "Altium Limited"))
      (libsource (lib "Miscellaneous Connectors") (part "Socket"))
    )
    (comp (ref "P1")
      (value "Header 6")
      (footprint "HDR1X6")
      (description "Header, 6-Pin")
      (fields (field (name "PUBLISHER") "Altium Limited"))
      (libsource (lib "") (part "Header 6_1"))
    )
    (comp (ref "P2")
      (value "Header 6")
      (footprint "HDR1X6")
      (description "Header, 6-Pin")
      (fields (field (name "PUBLISHER") "Altium Limited"))
      (libsource (lib "") (part "Header 6_1"))
    )
    (comp (ref "P3")
      (value "TEMP2")
      (footprint "3PIN")
      (description "Header, 3-Pin")
      (fields (field (name "PUBLISHER") "Altium Limited"))
      (libsource (lib "Miscellaneous Connectors") (part "Header 3"))
    )
    (comp (ref "P4")
      (value "TEMP3")
      (footprint "3PIN")
      (description "Header, 3-Pin")
      (fields (field (name "PUBLISHER") "Altium Limited"))
      (libsource (lib "Miscellaneous Connectors") (part "Header 3"))
    )
    (comp (ref "POWER_IN1")
      (value "Header 5X2A")
      (footprint "PWR_10PIN")
      (description "Header, 5-Pin, Dual row")
      (fields (field (name "PUBLISHER") "Altium Limited"))
      (libsource (lib "Miscellaneous Connectors") (part "Header 5X2A"))
    )
    (comp (ref "PROG")
      (value "SW-PB")
      (footprint "SKQMA")
      (description "Switch")
      (fields (field (name "PUBLISHER") "Altium Limited"))
      (libsource (lib "Miscellaneous Devices") (part "SW-PB"))
    )
    (comp (ref "Q1")
      (value "MMBT3904")
      (footprint "SOT23_L")
      (description "NPN Switching Transistor")
      (fields (field (name "PUBLISHER") "Altium Limited"))
      (libsource (lib "Philips Discrete BJT - Low Power") (part "MMBT3904"))
    )
    (comp (ref "Q2")
      (value "MMBT3904")
      (footprint "SOT23_L")
      (description "NPN Switching Transistor")
      (fields (field (name "PUBLISHER") "Altium Limited"))
      (libsource (lib "Philips Discrete BJT - Low Power") (part "MMBT3904"))
    )
    (comp (ref "R1")
      (value "MB")
      (footprint "RESC1005L")
      (description "Resistor")
      (fields (field (name "PUBLISHER") "Altium Limited"))
      (libsource (lib "Miscellaneous Devices") (part "Res3"))
    )
    (comp (ref "R2")
      (value "0R")
      (footprint "RESC1005L")
      (description "Resistor")
      (fields (field (name "PUBLISHER") "Altium Limited"))
      (libsource (lib "Miscellaneous Devices") (part "Res3"))
    )
    (comp (ref "R3")
      (value "10K")
      (footprint "RESC1005L")
      (description "Resistor")
      (fields (field (name "PUBLISHER") "Altium Limited"))
      (libsource (lib "Miscellaneous Devices") (part "Res3"))
    )
    (comp (ref "R4")
      (value "MB")
      (footprint "RESC1005L")
      (description "Resistor")
      (fields (field (name "PUBLISHER") "Altium Limited"))
      (libsource (lib "Miscellaneous Devices") (part "Res3"))
    )
    (comp (ref "R5")
      (value "MB")
      (footprint "RESC1005L")
      (description "Resistor")
      (fields (field (name "PUBLISHER") "Altium Limited"))
      (libsource (lib "Miscellaneous Devices") (part "Res3"))
    )
    (comp (ref "R6")
      (value "1M")
      (footprint "RESC1005L")
      (description "Resistor")
      (fields (field (name "PUBLISHER") "Altium Limited"))
      (libsource (lib "Miscellaneous Devices") (part "Res3"))
    )
    (comp (ref "R7")
      (value "0R")
      (footprint "RESC1005L")
      (description "Resistor")
      (fields (field (name "PUBLISHER") "Altium Limited"))
      (libsource (lib "Miscellaneous Devices") (part "Res3"))
    )
    (comp (ref "R8")
      (value "MB")
      (footprint "RESC1005L")
      (description "Resistor")
      (fields (field (name "PUBLISHER") "Altium Limited"))
      (libsource (lib "Miscellaneous Devices") (part "Res3"))
    )
    (comp (ref "R9")
      (value "1K")
      (footprint "RESC1005L")
      (description "Resistor")
      (fields (field (name "PUBLISHER") "Altium Limited"))
      (libsource (lib "Miscellaneous Devices") (part "Res3"))
    )
    (comp (ref "R10")
      (value "270R")
      (footprint "RESC1005L")
      (description "Resistor")
      (fields (field (name "PUBLISHER") "Altium Limited"))
      (libsource (lib "Miscellaneous Devices") (part "Res3"))
    )
    (comp (ref "R11")
      (value "MB")
      (footprint "RESC1005L")
      (description "Resistor")
      (fields (field (name "PUBLISHER") "Altium Limited"))
      (libsource (lib "Miscellaneous Devices") (part "Res3"))
    )
    (comp (ref "R12")
      (value "4.7K")
      (footprint "RESC1005L")
      (description "Resistor")
      (fields (field (name "PUBLISHER") "Altium Limited"))
      (libsource (lib "Miscellaneous Devices") (part "Res3"))
    )
    (comp (ref "R13")
      (value "MB")
      (footprint "RESC1005L")
      (description "Resistor")
      (fields (field (name "PUBLISHER") "Altium Limited"))
      (libsource (lib "Miscellaneous Devices") (part "Res3"))
    )
    (comp (ref "R14")
      (value "2.43K")
      (footprint "RESC1005L")
      (description "Resistor")
      (fields (field (name "PUBLISHER") "Altium Limited"))
      (libsource (lib "Miscellaneous Devices") (part "Res3"))
    )
    (comp (ref "R15")
      (value "10K")
      (footprint "RESC1005L")
      (description "Resistor")
      (fields (field (name "PUBLISHER") "Altium Limited"))
      (libsource (lib "Miscellaneous Devices") (part "Res3"))
    )
    (comp (ref "R16")
      (value "10K")
      (footprint "RESC1005L")
      (description "Resistor")
      (fields (field (name "PUBLISHER") "Altium Limited"))
      (libsource (lib "Miscellaneous Devices") (part "Res3"))
    )
    (comp (ref "R17")
      (value "4.7K")
      (footprint "RESC1005L")
      (description "Resistor")
      (fields (field (name "PUBLISHER") "Altium Limited"))
      (libsource (lib "Miscellaneous Devices") (part "Res3"))
    )
    (comp (ref "R18")
      (value "510R")
      (footprint "RESC1005L")
      (description "Resistor")
      (fields (field (name "PUBLISHER") "Altium Limited"))
      (libsource (lib "Miscellaneous Devices") (part "Res3"))
    )
    (comp (ref "R19")
      (value "10K")
      (footprint "RESC1005L")
      (description "Resistor")
      (fields (field (name "PUBLISHER") "Altium Limited"))
      (libsource (lib "Miscellaneous Devices") (part "Res3"))
    )
    (comp (ref "R20")
      (value "510R")
      (footprint "RESC1005L")
      (description "Resistor")
      (fields (field (name "PUBLISHER") "Altium Limited"))
      (libsource (lib "Miscellaneous Devices") (part "Res3"))
    )
    (comp (ref "R21")
      (value "1K")
      (footprint "RESC1005L")
      (description "Resistor")
      (fields (field (name "PUBLISHER") "Altium Limited"))
      (libsource (lib "Miscellaneous Devices") (part "Res3"))
    )
    (comp (ref "R22")
      (value "270R")
      (footprint "RESC1005L")
      (description "Resistor")
      (fields (field (name "PUBLISHER") "Altium Limited"))
      (libsource (lib "Miscellaneous Devices") (part "Res3"))
    )
    (comp (ref "R23")
      (value "MB")
      (footprint "RESC1005L")
      (description "Resistor")
      (fields (field (name "PUBLISHER") "Altium Limited"))
      (libsource (lib "Miscellaneous Devices") (part "Res3"))
    )
    (comp (ref "R24")
      (value "MB")
      (footprint "RESC1005L")
      (description "Resistor")
      (fields (field (name "PUBLISHER") "Altium Limited"))
      (libsource (lib "Miscellaneous Devices") (part "Res3"))
    )
    (comp (ref "R25")
      (value "4.7K")
      (footprint "RESC1005L")
      (description "Resistor")
      (fields (field (name "PUBLISHER") "Altium Limited"))
      (libsource (lib "Miscellaneous Devices") (part "Res3"))
    )
    (comp (ref "R26")
      (value "4.7K")
      (footprint "RESC1005L")
      (description "Resistor")
      (fields (field (name "PUBLISHER") "Altium Limited"))
      (libsource (lib "Miscellaneous Devices") (part "Res3"))
    )
    (comp (ref "R27")
      (value "10K")
      (footprint "RESC1005L")
      (description "Resistor")
      (fields (field (name "PUBLISHER") "Altium Limited"))
      (libsource (lib "Miscellaneous Devices") (part "Res3"))
    )
    (comp (ref "R28")
      (value "100R")
      (footprint "RESC1005L")
      (description "Resistor")
      (fields (field (name "PUBLISHER") "Altium Limited"))
      (libsource (lib "Miscellaneous Devices") (part "Res3"))
    )
    (comp (ref "R29")
      (value "100R")
      (footprint "RESC1005L")
      (description "Resistor")
      (fields (field (name "PUBLISHER") "Altium Limited"))
      (libsource (lib "Miscellaneous Devices") (part "Res3"))
    )
    (comp (ref "R30")
      (value "4.7K")
      (footprint "RESC1005L")
      (description "Resistor")
      (fields (field (name "PUBLISHER") "Altium Limited"))
      (libsource (lib "Miscellaneous Devices") (part "Res3"))
    )
    (comp (ref "R31")
      (value "10K")
      (footprint "RESC1005L")
      (description "Resistor")
      (fields (field (name "PUBLISHER") "Altium Limited"))
      (libsource (lib "Miscellaneous Devices") (part "Res3"))
    )
    (comp (ref "R32")
      (value "4.7K")
      (footprint "RESC1005L")
      (description "Resistor")
      (fields (field (name "PUBLISHER") "Altium Limited"))
      (libsource (lib "Miscellaneous Devices") (part "Res3"))
    )
    (comp (ref "R33")
      (value "NC")
      (footprint "RESC1005L")
      (description "Resistor")
      (fields (field (name "PUBLISHER") "Altium Limited"))
      (libsource (lib "Miscellaneous Devices") (part "Res3"))
    )
    (comp (ref "R34")
      (value "NC")
      (footprint "RESC1005L")
      (description "Resistor")
      (fields (field (name "PUBLISHER") "Altium Limited"))
      (libsource (lib "Miscellaneous Devices") (part "Res3"))
    )
    (comp (ref "R35")
      (value "MB")
      (footprint "RESC1005L")
      (description "Resistor")
      (fields (field (name "PUBLISHER") "Altium Limited"))
      (libsource (lib "Miscellaneous Devices") (part "Res3"))
    )
    (comp (ref "R36")
      (value "100R")
      (footprint "RESC1005L")
      (description "Resistor")
      (fields (field (name "PUBLISHER") "Altium Limited"))
      (libsource (lib "Miscellaneous Devices") (part "Res3"))
    )
    (comp (ref "R37")
      (value "4.7K")
      (footprint "RESC1005L")
      (description "Resistor")
      (fields (field (name "PUBLISHER") "Altium Limited"))
      (libsource (lib "Miscellaneous Devices") (part "Res3"))
    )
    (comp (ref "R38")
      (value "4.7K")
      (footprint "RESC1005L")
      (description "Resistor")
      (fields (field (name "PUBLISHER") "Altium Limited"))
      (libsource (lib "Miscellaneous Devices") (part "Res3"))
    )
    (comp (ref "R39")
      (value "4.7K")
      (footprint "RESC1005L")
      (description "Resistor")
      (fields (field (name "PUBLISHER") "Altium Limited"))
      (libsource (lib "Miscellaneous Devices") (part "Res3"))
    )
    (comp (ref "R40")
      (value "4.7K")
      (footprint "RESC1005L")
      (description "Resistor")
      (fields (field (name "PUBLISHER") "Altium Limited"))
      (libsource (lib "Miscellaneous Devices") (part "Res3"))
    )
    (comp (ref "R41")
      (value "4.7K")
      (footprint "RESC1005L")
      (description "Resistor")
      (fields (field (name "PUBLISHER") "Altium Limited"))
      (libsource (lib "Miscellaneous Devices") (part "Res3"))
    )
    (comp (ref "R42")
      (value "10K")
      (footprint "RESC1005L")
      (description "Resistor")
      (fields (field (name "PUBLISHER") "Altium Limited"))
      (libsource (lib "Miscellaneous Devices") (part "Res3"))
    )
    (comp (ref "R43")
      (value "100R")
      (footprint "RESC1005L")
      (description "Resistor")
      (fields (field (name "PUBLISHER") "Altium Limited"))
      (libsource (lib "Miscellaneous Devices") (part "Res3"))
    )
    (comp (ref "R44")
      (value "100R")
      (footprint "RESC1005L")
      (description "Resistor")
      (fields (field (name "PUBLISHER") "Altium Limited"))
      (libsource (lib "Miscellaneous Devices") (part "Res3"))
    )
    (comp (ref "R45")
      (value "1.8K")
      (footprint "RESC1005L")
      (description "Resistor")
      (fields (field (name "PUBLISHER") "Altium Limited"))
      (libsource (lib "Miscellaneous Devices") (part "Res3"))
    )
    (comp (ref "R46")
      (value "4.7K")
      (footprint "RESC1005L")
      (description "Resistor")
      (fields (field (name "PUBLISHER") "Altium Limited"))
      (libsource (lib "Miscellaneous Devices") (part "Res3"))
    )
    (comp (ref "R47")
      (value "1.8K")
      (footprint "RESC1005L")
      (description "Resistor")
      (fields (field (name "PUBLISHER") "Altium Limited"))
      (libsource (lib "Miscellaneous Devices") (part "Res3"))
    )
    (comp (ref "R48")
      (value "510R")
      (footprint "RESC1005L")
      (description "Resistor")
      (fields (field (name "PUBLISHER") "Altium Limited"))
      (libsource (lib "Miscellaneous Devices") (part "Res3"))
    )
    (comp (ref "R49")
      (value "100R")
      (footprint "RESC1005L")
      (description "Resistor")
      (fields (field (name "PUBLISHER") "Altium Limited"))
      (libsource (lib "Miscellaneous Devices") (part "Res3"))
    )
    (comp (ref "R50")
      (value "4.7K")
      (footprint "RESC1005L")
      (description "Resistor")
      (fields (field (name "PUBLISHER") "Altium Limited"))
      (libsource (lib "Miscellaneous Devices") (part "Res3"))
    )
    (comp (ref "R51")
      (value "4.7K")
      (footprint "RESC1005L")
      (description "Resistor")
      (fields (field (name "PUBLISHER") "Altium Limited"))
      (libsource (lib "Miscellaneous Devices") (part "Res3"))
    )
    (comp (ref "R52")
      (value "4.7K")
      (footprint "RESC1005L")
      (description "Resistor")
      (fields (field (name "PUBLISHER") "Altium Limited"))
      (libsource (lib "Miscellaneous Devices") (part "Res3"))
    )
    (comp (ref "R53")
      (value "4.7K")
      (footprint "RESC1005L")
      (description "Resistor")
      (fields (field (name "PUBLISHER") "Altium Limited"))
      (libsource (lib "Miscellaneous Devices") (part "Res3"))
    )
    (comp (ref "R54")
      (value "4.7K")
      (footprint "RESC1005L")
      (description "Resistor")
      (fields (field (name "PUBLISHER") "Altium Limited"))
      (libsource (lib "Miscellaneous Devices") (part "Res3"))
    )
    (comp (ref "R55")
      (value "270R")
      (footprint "RESC1005L")
      (description "Resistor")
      (fields (field (name "PUBLISHER") "Altium Limited"))
      (libsource (lib "Miscellaneous Devices") (part "Res3"))
    )
    (comp (ref "R56")
      (value "100R")
      (footprint "RESC1005L")
      (description "Resistor")
      (fields (field (name "PUBLISHER") "Altium Limited"))
      (libsource (lib "Miscellaneous Devices") (part "Res3"))
    )
    (comp (ref "R57")
      (value "10K")
      (footprint "RESC1005L")
      (description "Resistor")
      (fields (field (name "PUBLISHER") "Altium Limited"))
      (libsource (lib "Miscellaneous Devices") (part "Res3"))
    )
    (comp (ref "R58")
      (value "100R")
      (footprint "RESC1005L")
      (description "Resistor")
      (fields (field (name "PUBLISHER") "Altium Limited"))
      (libsource (lib "Miscellaneous Devices") (part "Res3"))
    )
    (comp (ref "R59")
      (value "4.7K")
      (footprint "RESC1005L")
      (description "Resistor")
      (fields (field (name "PUBLISHER") "Altium Limited"))
      (libsource (lib "Miscellaneous Devices") (part "Res3"))
    )
    (comp (ref "R60")
      (value "100R")
      (footprint "RESC1005L")
      (description "Resistor")
      (fields (field (name "PUBLISHER") "Altium Limited"))
      (libsource (lib "Miscellaneous Devices") (part "Res3"))
    )
    (comp (ref "R61")
      (value "4.7K")
      (footprint "RESC1005L")
      (description "Resistor")
      (fields (field (name "PUBLISHER") "Altium Limited"))
      (libsource (lib "Miscellaneous Devices") (part "Res3"))
    )
    (comp (ref "R62")
      (value "270R")
      (footprint "RESC1005L")
      (description "Resistor")
      (fields (field (name "PUBLISHER") "Altium Limited"))
      (libsource (lib "Miscellaneous Devices") (part "Res3"))
    )
    (comp (ref "R63")
      (value "270R")
      (footprint "RESC1005L")
      (description "Resistor")
      (fields (field (name "PUBLISHER") "Altium Limited"))
      (libsource (lib "Miscellaneous Devices") (part "Res3"))
    )
    (comp (ref "R64")
      (value "270R")
      (footprint "RESC1005L")
      (description "Resistor")
      (fields (field (name "PUBLISHER") "Altium Limited"))
      (libsource (lib "Miscellaneous Devices") (part "Res3"))
    )
    (comp (ref "R65")
      (value "4.7K")
      (footprint "RESC1005L")
      (description "Resistor")
      (fields (field (name "PUBLISHER") "Altium Limited"))
      (libsource (lib "Miscellaneous Devices") (part "Res3"))
    )
    (comp (ref "R66")
      (value "270R")
      (footprint "RESC1005L")
      (description "Resistor")
      (fields (field (name "PUBLISHER") "Altium Limited"))
      (libsource (lib "Miscellaneous Devices") (part "Res3"))
    )
    (comp (ref "RN1") (value "330R") (footprint "EXBV8V") (libsource (lib "") (part "RES4PACK_2")))
    (comp (ref "RN2") (value "100R") (footprint "EXBV8V") (libsource (lib "") (part "RES4PACK_1")))
    (comp (ref "RN3") (value "100R") (footprint "EXBV8V") (libsource (lib "S6") (part "RES4PACK")))
    (comp (ref "RTS") (value "TP") (footprint "TP") (libsource (lib "S6") (part "TP")))
    (comp (ref "RXD") (value "TP") (footprint "TP") (libsource (lib "S6") (part "TP")))
    (comp (ref "TPM1") (value "MASKTEST") (footprint "MASKTEST") (libsource (lib "S6_2") (part "MASKTEST")))
    (comp (ref "TPM2") (value "MASKTEST") (footprint "MASKTEST") (libsource (lib "S6_2") (part "MASKTEST")))
    (comp (ref "TXD") (value "TP") (footprint "TP") (libsource (lib "S6") (part "TP")))
    (comp (ref "U1")
      (value "XC6SLX16-2FTG256C")
      (footprint "FTG256_L")
      (fields (field (name "PUBLISHER") "Altium Limited"))
      (libsource (lib "Xilinx Spartan-6") (part "XC6SLX16-2FTG256C"))
    )
    (comp (ref "U2")
      (value "LM1086CS-3.3")
      (footprint "TS3B_M")
      (description "1.5A Low Dropout Positive Regulators, 3-pin TO-263")
      (fields
        (field (name "PARTNUMBER") "LM1086CS-2.5")
        (field (name "MANUFACTURER") "National Semiconductor")
        (field (name "PUBLISHER") "Altium Limited")
      )
      (libsource (lib "NSC LDO") (part "LM1086CS-2.5"))
    )
    (comp (ref "U3")
      (value "RT9166A_CXL")
      (footprint "SOT-89_M")
      (libsource (lib "S6_2") (part "RT9166A_CXL"))
    )
    (comp (ref "U4") (value "μPD720114") (footprint "TQFP48_L") (libsource (lib "S6_2") (part "uPD720114")))
    (comp (ref "U5")
      (value "FT232RQ-Tray")
      (footprint "PQFN5X5-32_V_M")
      (description "USB UART Asynchronous Serial Data Transfer Chip, QFN-32, Tray")
      (fields (field (name "PUBLISHER") "Altium Limited"))
      (libsource (lib "FTDI Communication UART") (part "FT232RQ-Tray"))
    )
    (comp (ref "U6") (value "W25Q80BV") (footprint "WSOP8") (libsource (lib "S6") (part "W25Q64CV")))
    (comp (ref "U7") (value "DS18B20") (footprint "TO-92_M") (libsource (lib "S6_2") (part "DS18B20")))
    (comp (ref "USB-A1")
      (value "1364428-1")
      (footprint "1364428")
      (description "USB 1.1, Vertical, Thru-Hole, A Type, Receptacle, 4 Position, Black")
      (fields (field (name "PUBLISHER") "Altium Limited"))
      (libsource (lib "AMP Serial Bus USB") (part "1364428-1"))
    )
    (comp (ref "USB-B1")
      (value "1470156-1")
      (footprint "1470156")
      (description "USB 1.1, Right Angle, Thru-Hole, B Type, Receptacle, 4 Position, White")
      (fields (field (name "PUBLISHER") "Altium Limited"))
      (libsource (lib "AMP Serial Bus USB") (part "1470156-1"))
    )
    (comp (ref "Y1")
      (value "2SMX")
      (footprint "SMX2")
      (description "Surface Mount Quartz Crystal")
      (fields (field (name "PUBLISHER") "Altium Limited"))
      (libsource (lib "C-MAC Crystal Oscillator") (part "2SMX"))
    )
    (comp (ref "Y2")
      (value "XTAL")
      (footprint "4SMX")
      (description "Crystal Oscillator")
      (fields (field (name "PUBLISHER") "Altium Limited"))
      (libsource (lib "Miscellaneous Devices") (part "XTAL"))
    )
  )
  (nets
    (net (code "1") (name "/CLK") (class "Default")
      (node (ref "R2") (pin "1") (pinfunction "1_1") (pintype "passive"))
      (node (ref "U1") (pin "K12") (pinfunction "IO_L42P_GCLK7_M1UDM_1_K12") (pintype "bidirectional"))
    )
    (net (code "2") (name "/D1_N") (class "Default")
      (node (ref "U4") (pin "25") (pinfunction "DM1_25") (pintype "passive"))
      (node (ref "U5") (pin "15") (pinfunction "USBDM_15") (pintype "bidirectional"))
    )
    (net (code "3") (name "/D1_P") (class "Default")
      (node (ref "U4") (pin "26") (pinfunction "DP1_26") (pintype "passive"))
      (node (ref "U5") (pin "14") (pinfunction "USBDP_14") (pintype "bidirectional"))
    )
    (net (code "4") (name "/D2_N") (class "Default")
      (node (ref "U4") (pin "28") (pinfunction "DM2_28") (pintype "passive"))
      (node (ref "USB-A1") (pin "2") (pinfunction "D-_2") (pintype "input"))
    )
    (net (code "5") (name "/D2_P") (class "Default")
      (node (ref "U4") (pin "29") (pinfunction "DP2_29") (pintype "passive"))
      (node (ref "USB-A1") (pin "3") (pinfunction "D+_3") (pintype "input"))
    )
    (net (code "6") (name "/DONE1") (class "Default")
      (node (ref "DONE") (pin "1") (pinfunction "A_1") (pintype "passive"))
      (node (ref "R48") (pin "2") (pinfunction "2_2") (pintype "passive"))
      (node (ref "U1") (pin "P13") (pinfunction "DONE_2_P13") (pintype "bidirectional"))
    )
    (net (code "7") (name "/FAN_PWM") (class "Default")
      (node (ref "Q1") (pin "3") (pinfunction "C_3") (pintype "passive"))
      (node (ref "R28") (pin "2") (pinfunction "2_2") (pintype "passive"))
      (node (ref "R43") (pin "2") (pinfunction "2_2") (pintype "passive"))
      (node (ref "R58") (pin "2") (pinfunction "2_2") (pintype "passive"))
    )
    (net (code "8") (name "/FAN_SPEED1") (class "Default")
      (node (ref "R60") (pin "1") (pinfunction "1_1") (pintype "passive"))
      (node (ref "U1") (pin "N16") (pinfunction "IO_L45N_A0_M1LDQSN_1_N16") (pintype "bidirectional"))
    )
    (net (code "9") (name "/FAN_SPEED2") (class "Default")
      (node (ref "R44") (pin "1") (pinfunction "1_1") (pintype "passive"))
      (node (ref "U1") (pin "P16") (pinfunction "IO_L48N_M1DQ9_1_P16") (pintype "bidirectional"))
    )
    (net (code "10") (name "/FAN_SPEED3") (class "Default")
      (node (ref "R29") (pin "1") (pinfunction "1_1") (pintype "passive"))
      (node (ref "U1") (pin "P15") (pinfunction "IO_L48P_HDC_M1DQ8_1_P15") (pintype "bidirectional"))
    )
    (net (code "11") (name "/FPGA1_CS") (class "Default")
      (node (ref "R40") (pin "2") (pinfunction "2_2") (pintype "passive"))
      (node (ref "U1") (pin "T3") (pinfunction "IO_L65N_CSO_B_2_T3") (pintype "bidirectional"))
      (node (ref "U6") (pin "1") (pinfunction "CS__1") (pintype "passive"))
    )
    (net (code "12") (name "/FPGA1_DQ0") (class "Default")
      (node (ref "RN3") (pin "8") (pinfunction "8_8") (pintype "power_in"))
      (node (ref "U1") (pin "P10") (pinfunction "IO_L3P_D0_DIN_MISO_MISO1_2_P10") (pintype "bidirectional"))
    )
    (net (code "13") (name "/FPGA1_DQ1") (class "Default")
      (node (ref "RN3") (pin "7") (pinfunction "7_7") (pintype "power_in"))
      (node (ref "U1") (pin "N12") (pinfunction "IO_L12P_D1_MISO2_2_N12") (pintype "bidirectional"))
    )
    (net (code "14") (name "/FPGA1_DQ2") (class "Default")
      (node (ref "RN3") (pin "5") (pinfunction "5_5") (pintype "power_in"))
      (node (ref "U1") (pin "P12") (pinfunction "IO_L12N_D2_MISO3_2_P12") (pintype "bidirectional"))
    )
    (net (code "15") (name "/FPGA1_HSWAP") (class "Default")
      (node (ref "R39") (pin "2") (pinfunction "2_2") (pintype "passive"))
      (node (ref "U1") (pin "C4") (pinfunction "IO_L1P_HSWAPEN_0_C4") (pintype "bidirectional"))
    )
    (net (code "16") (name "/FPGA1_INIT") (class "Default")
      (node (ref "R37") (pin "2") (pinfunction "2_2") (pintype "passive"))
      (node (ref "U1") (pin "R3") (pinfunction "IO_L65P_INIT_B_2_R3") (pintype "bidirectional"))
    )
    (net (code "17") (name "/FPGA1_LED1") (class "Default")
      (node (ref "RN1") (pin "5") (pinfunction "5_5") (pintype "power_in"))
      (node (ref "U1") (pin "J11") (pinfunction "IO_L40P_GCLK11_M1A5_1_J11") (pintype "bidirectional"))
    )
    (net (code "18") (name "/FPGA1_LED2") (class "Default")
      (node (ref "RN1") (pin "6") (pinfunction "6_6") (pintype "power_in"))
      (node (ref "U1") (pin "J12") (pinfunction "IO_L40N_GCLK10_M1A6_1_J12") (pintype "bidirectional"))
    )
    (net (code "19") (name "/FPGA1_LED3") (class "Default")
      (node (ref "RN1") (pin "7") (pinfunction "7_7") (pintype "power_in"))
      (node (ref "U1") (pin "J13") (pinfunction "IO_L41P_GCLK9_IRDY1_M1RASN_1_J13") (pintype "bidirectional"))
    )
    (net (code "20") (name "/FPGA1_LED4") (class "Default")
      (node (ref "RN1") (pin "8") (pinfunction "8_8") (pintype "power_in"))
      (node (ref "U1") (pin "J14") (pinfunction "IO_L43P_GCLK5_M1DQ4_1_J14") (pintype "bidirectional"))
    )
    (net (code "21") (name "/FPGA1_M0") (class "Default")
      (node (ref "R32") (pin "2") (pinfunction "2_2") (pintype "passive"))
      (node (ref "R33") (pin "2") (pinfunction "2_2") (pintype "passive"))
      (node (ref "U1") (pin "T11") (pinfunction "IO_L1N_M0_CMPMISO_2_T11") (pintype "bidirectional"))
    )
    (net (code "22") (name "/FPGA1_M1") (class "Default")
      (node (ref "R34") (pin "2") (pinfunction "2_2") (pintype "passive"))
      (node (ref "R36") (pin "2") (pinfunction "2_2") (pintype "passive"))
      (node (ref "U1") (pin "N11") (pinfunction "IO_L13P_M1_2_N11") (pintype "bidirectional"))
    )
    (net (code "23") (name "/FPGA1_SCK") (class "Default")
      (node (ref "R49") (pin "2") (pinfunction "2_2") (pintype "passive"))
      (node (ref "R56") (pin "1") (pinfunction "1_1") (pintype "passive"))
      (node (ref "U1") (pin "R11") (pinfunction "IO_L1P_CCLK_2_R11") (pintype "bidirectional"))
      (node (ref "U6") (pin "6") (pinfunction "CLK_6") (pintype "passive"))
    )
    (net (code "24") (name "/FPGA1_SDI") (class "Default")
      (node (ref "RN3") (pin "6") (pinfunction "6_6") (pintype "power_in"))
      (node (ref "U1") (pin "T10") (pinfunction "IO_L3N_MOSI_CSI_B_MISO0_2_T10") (pintype "bidirectional"))
    )
    (net (code "25") (name "/FPGA_A2") (class "Default")
      (node (ref "DATA_P2") (pin "8") (pinfunction "8_8") (pintype "passive"))
      (node (ref "U1") (pin "A2") (pinfunction "IO_L52N_M3A9_3_A2") (pintype "bidirectional"))
    )
    (net (code "26") (name "/FPGA_A3") (class "Default")
      (node (ref "DATA_P2") (pin "10") (pinfunction "10_10") (pintype "passive"))
      (node (ref "U1") (pin "A3") (pinfunction "IO_L83N_VREF_3_A3") (pintype "bidirectional"))
    )
    (net (code "27") (name "/FPGA_A4") (class "Default")
      (node (ref "DATA_P2") (pin "9") (pinfunction "9_9") (pintype "passive"))
      (node (ref "U1") (pin "A4") (pinfunction "IO_L1N_VREF_0_A4") (pintype "bidirectional"))
    )
    (net (code "28") (name "/FPGA_A5") (class "Default")
      (node (ref "DATA_P1") (pin "3") (pinfunction "3_3") (pintype "passive"))
      (node (ref "U1") (pin "A5") (pinfunction "IO_L2N_0_A5") (pintype "bidirectional"))
    )
    (net (code "29") (name "/FPGA_A6") (class "Default")
      (node (ref "DATA_P1") (pin "5") (pinfunction "5_5") (pintype "passive"))
      (node (ref "U1") (pin "A6") (pinfunction "IO_L4N_0_A6") (pintype "bidirectional"))
    )
    (net (code "30") (name "/FPGA_A7") (class "Default")
      (node (ref "DATA_P1") (pin "8") (pinfunction "8_8") (pintype "passive"))
      (node (ref "U1") (pin "A7") (pinfunction "IO_L6N_0_A7") (pintype "bidirectional"))
    )
    (net (code "31") (name "/FPGA_A8") (class "Default")
      (node (ref "DATA_P1") (pin "10") (pinfunction "10_10") (pintype "passive"))
      (node (ref "U1") (pin "A8") (pinfunction "IO_L33N_0_A8") (pintype "bidirectional"))
    )
    (net (code "32") (name "/FPGA_A9") (class "Default")
      (node (ref "DATA_P1") (pin "12") (pinfunction "12_12") (pintype "passive"))
      (node (ref "U1") (pin "A9") (pinfunction "IO_L34N_GCLK18_0_A9") (pintype "bidirectional"))
    )
    (net (code "33") (name "/FPGA_A10") (class "Default")
      (node (ref "DATA_P2") (pin "16") (pinfunction "16_16") (pintype "passive"))
      (node (ref "U1") (pin "A10") (pinfunction "IO_L35N_GCLK16_0_A10") (pintype "bidirectional"))
    )
    (net (code "34") (name "/FPGA_A11") (class "Default")
      (node (ref "DATA_P2") (pin "15") (pinfunction "15_15") (pintype "passive"))
      (node (ref "U1") (pin "A11") (pinfunction "IO_L39N_0_A11") (pintype "bidirectional"))
    )
    (net (code "35") (name "/FPGA_A12") (class "Default")
      (node (ref "DATA_P1") (pin "16") (pinfunction "16_16") (pintype "passive"))
      (node (ref "U1") (pin "A12") (pinfunction "IO_L62N_VREF_0_A12") (pintype "bidirectional"))
    )
    (net (code "36") (name "/FPGA_A13") (class "Default")
      (node (ref "DATA_P1") (pin "18") (pinfunction "18_18") (pintype "passive"))
      (node (ref "U1") (pin "A13") (pinfunction "IO_L63N_SCP6_0_A13") (pintype "bidirectional"))
    )
    (net (code "37") (name "/FPGA_A14") (class "Default")
      (node (ref "DATA_P1") (pin "17") (pinfunction "17_17") (pintype "passive"))
      (node (ref "U1") (pin "A14") (pinfunction "IO_L65N_SCP2_0_A14") (pintype "bidirectional"))
    )
    (net (code "38") (name "/FPGA_B1") (class "Default")
      (node (ref "DATA_P2") (pin "6") (pinfunction "6_6") (pintype "passive"))
      (node (ref "U1") (pin "B1") (pinfunction "IO_L50N_M3BA2_3_B1") (pintype "bidirectional"))
    )
    (net (code "39") (name "/FPGA_B2") (class "Default")
      (node (ref "DATA_P2") (pin "5") (pinfunction "5_5") (pintype "passive"))
      (node (ref "U1") (pin "B2") (pinfunction "IO_L52P_M3A8_3_B2") (pintype "bidirectional"))
    )
    (net (code "40") (name "/FPGA_B3") (class "Default")
      (node (ref "DATA_P2") (pin "7") (pinfunction "7_7") (pintype "passive"))
      (node (ref "U1") (pin "B3") (pinfunction "IO_L83P_3_B3") (pintype "bidirectional"))
    )
    (net (code "41") (name "/FPGA_B5") (class "Default")
      (node (ref "DATA_P2") (pin "12") (pinfunction "12_12") (pintype "passive"))
      (node (ref "U1") (pin "B5") (pinfunction "IO_L2P_0_B5") (pintype "bidirectional"))
    )
    (net (code "42") (name "/FPGA_B6") (class "Default")
      (node (ref "DATA_P2") (pin "11") (pinfunction "11_11") (pintype "passive"))
      (node (ref "U1") (pin "B6") (pinfunction "IO_L4P_0_B6") (pintype "bidirectional"))
    )
    (net (code "43") (name "/FPGA_B8") (class "Default")
      (node (ref "DATA_P2") (pin "14") (pinfunction "14_14") (pintype "passive"))
      (node (ref "U1") (pin "B8") (pinfunction "IO_L33P_0_B8") (pintype "bidirectional"))
    )
    (net (code "44") (name "/FPGA_B10") (class "Default")
      (node (ref "DATA_P1") (pin "11") (pinfunction "11_11") (pintype "passive"))
      (node (ref "U1") (pin "B10") (pinfunction "IO_L35P_GCLK17_0_B10") (pintype "bidirectional"))
    )
    (net (code "45") (name "/FPGA_B12") (class "Default")
      (node (ref "DATA_P1") (pin "15") (pinfunction "15_15") (pintype "passive"))
      (node (ref "U1") (pin "B12") (pinfunction "IO_L62P_0_B12") (pintype "bidirectional"))
    )
    (net (code "46") (name "/FPGA_B14") (class "Default")
      (node (ref "DATA_P2") (pin "17") (pinfunction "17_17") (pintype "passive"))
      (node (ref "U1") (pin "B14") (pinfunction "IO_L65P_SCP3_0_B14") (pintype "bidirectional"))
    )
    (net (code "47") (name "/FPGA_B15") (class "Default")
      (node (ref "DATA_P2") (pin "20") (pinfunction "20_20") (pintype "passive"))
      (node (ref "U1") (pin "B15") (pinfunction "IO_L29P_A23_M1A13_1_B15") (pintype "bidirectional"))
    )
    (net (code "48") (name "/FPGA_B16") (class "Default")
      (node (ref "DATA_P1") (pin "21") (pinfunction "21_21") (pintype "passive"))
      (node (ref "U1") (pin "B16") (pinfunction "IO_L29N_A22_M1A14_1_B16") (pintype "bidirectional"))
    )
    (net (code "49") (name "/FPGA_C1") (class "Default")
      (node (ref "DATA_P2") (pin "1") (pinfunction "1_1") (pintype "passive"))
      (node (ref "U1") (pin "C1") (pinfunction "IO_L50P_M3WE_3_C1") (pintype "bidirectional"))
    )
    (net (code "50") (name "/FPGA_C2") (class "Default")
      (node (ref "DATA_P2") (pin "4") (pinfunction "4_4") (pintype "passive"))
      (node (ref "U1") (pin "C2") (pinfunction "IO_L48N_M3BA1_3_C2") (pintype "bidirectional"))
    )
    (net (code "51") (name "/FPGA_C3") (class "Default")
      (node (ref "DATA_P2") (pin "3") (pinfunction "3_3") (pintype "passive"))
      (node (ref "U1") (pin "C3") (pinfunction "IO_L48P_M3BA0_3_C3") (pintype "bidirectional"))
    )
    (net (code "52") (name "/FPGA_C5") (class "Default")
      (node (ref "DATA_P1") (pin "4") (pinfunction "4_4") (pintype "passive"))
      (node (ref "U1") (pin "C5") (pinfunction "IO_L3N_0_C5") (pintype "bidirectional"))
    )
    (net (code "53") (name "/FPGA_C6") (class "Default")
      (node (ref "DATA_P1") (pin "6") (pinfunction "6_6") (pintype "passive"))
      (node (ref "U1") (pin "C6") (pinfunction "IO_L7N_0_C6") (pintype "bidirectional"))
    )
    (net (code "54") (name "/FPGA_C7") (class "Default")
      (node (ref "DATA_P1") (pin "7") (pinfunction "7_7") (pintype "passive"))
      (node (ref "U1") (pin "C7") (pinfunction "IO_L6P_0_C7") (pintype "bidirectional"))
    )
    (net (code "55") (name "/FPGA_C8") (class "Default")
      (node (ref "DATA_P1") (pin "9") (pinfunction "9_9") (pintype "passive"))
      (node (ref "U1") (pin "C8") (pinfunction "IO_L38N_VREF_0_C8") (pintype "bidirectional"))
    )
    (net (code "56") (name "/FPGA_C9") (class "Default")
      (node (ref "DATA_P2") (pin "13") (pinfunction "13_13") (pintype "passive"))
      (node (ref "U1") (pin "C9") (pinfunction "IO_L34P_GCLK19_0_C9") (pintype "bidirectional"))
    )
    (net (code "57") (name "/FPGA_C10") (class "Default")
      (node (ref "DATA_P1") (pin "14") (pinfunction "14_14") (pintype "passive"))
      (node (ref "U1") (pin "C10") (pinfunction "IO_L37N_GCLK12_0_C10") (pintype "bidirectional"))
    )
    (net (code "58") (name "/FPGA_C11") (class "Default")
      (node (ref "DATA_P1") (pin "13") (pinfunction "13_13") (pintype "passive"))
      (node (ref "U1") (pin "C11") (pinfunction "IO_L39P_0_C11") (pintype "bidirectional"))
    )
    (net (code "59") (name "/FPGA_C13") (class "Default")
      (node (ref "DATA_P2") (pin "18") (pinfunction "18_18") (pintype "passive"))
      (node (ref "U1") (pin "C13") (pinfunction "IO_L63P_SCP7_0_C13") (pintype "bidirectional"))
    )
    (net (code "60") (name "/FPGA_C15") (class "Default")
      (node (ref "DATA_P2") (pin "21") (pinfunction "21_21") (pintype "passive"))
      (node (ref "U1") (pin "C15") (pinfunction "IO_L33P_A15_M1A10_1_C15") (pintype "bidirectional"))
    )
    (net (code "61") (name "/FPGA_C16") (class "Default")
      (node (ref "DATA_P2") (pin "23") (pinfunction "23_23") (pintype "passive"))
      (node (ref "U1") (pin "C16") (pinfunction "IO_L33N_A14_M1A4_1_C16") (pintype "bidirectional"))
    )
    (net (code "62") (name "/FPGA_D1") (class "Default")
      (node (ref "DATA_P3") (pin "3") (pinfunction "3_3") (pintype "passive"))
      (node (ref "U1") (pin "D1") (pinfunction "IO_L49N_M3A2_3_D1") (pintype "bidirectional"))
    )
    (net (code "63") (name "/FPGA_D3") (class "Default")
      (node (ref "DATA_P4") (pin "7") (pinfunction "7_7") (pintype "passive"))
      (node (ref "U1") (pin "D3") (pinfunction "IO_L49P_M3A7_3_D3") (pintype "bidirectional"))
    )
    (net (code "64") (name "/FPGA_D5") (class "Default")
      (node (ref "DATA_P1") (pin "1") (pinfunction "1_1") (pintype "passive"))
      (node (ref "U1") (pin "D5") (pinfunction "IO_L3P_0_D5") (pintype "bidirectional"))
    )
    (net (code "65") (name "/FPGA_D6") (class "Default")
      (node (ref "DATA_P4") (pin "5") (pinfunction "5_5") (pintype "passive"))
      (node (ref "U1") (pin "D6") (pinfunction "IO_L7P_0_D6") (pintype "bidirectional"))
    )
    (net (code "66") (name "/FPGA_D8") (class "Default")
      (node (ref "DATA_P3") (pin "1") (pinfunction "1_1") (pintype "passive"))
      (node (ref "U1") (pin "D8") (pinfunction "IO_L38P_0_D8") (pintype "bidirectional"))
    )
    (net (code "67") (name "/FPGA_D9") (class "Default")
      (node (ref "DATA_P4") (pin "1") (pinfunction "1_1") (pintype "passive"))
      (node (ref "U1") (pin "D9") (pinfunction "IO_L40N_0_D9") (pintype "bidirectional"))
    )
    (net (code "68") (name "/FPGA_D11") (class "Default")
      (node (ref "U1") (pin "D11") (pinfunction "IO_L66P_SCP1_0_D11") (pintype "bidirectional"))
    )
    (net (code "69") (name "/FPGA_D12") (class "Default")
      (node (ref "U1") (pin "D12") (pinfunction "IO_L66N_SCP0_0_D12") (pintype "bidirectional"))
    )
    (net (code "70") (name "/FPGA_D14") (class "Default")
      (node (ref "DATA_P1") (pin "20") (pinfunction "20_20") (pintype "passive"))
      (node (ref "U1") (pin "D14") (pinfunction "IO_L31P_A19_M1CKE_1_D14") (pintype "bidirectional"))
    )
    (net (code "71") (name "/FPGA_D16") (class "Default")
      (node (ref "DATA_P2") (pin "25") (pinfunction "25_25") (pintype "passive"))
      (node (ref "U1") (pin "D16") (pinfunction "IO_L31N_A18_M1A12_1_D16") (pintype "bidirectional"))
    )
    (net (code "72") (name "/FPGA_E1") (class "Default")
      (node (ref "DATA_P3") (pin "6") (pinfunction "6_6") (pintype "passive"))
      (node (ref "U1") (pin "E1") (pinfunction "IO_L46N_M3CLKN_3_E1") (pintype "bidirectional"))
    )
    (net (code "73") (name "/FPGA_E2") (class "Default")
      (node (ref "DATA_P3") (pin "5") (pinfunction "5_5") (pintype "passive"))
      (node (ref "U1") (pin "E2") (pinfunction "IO_L46P_M3CLK_3_E2") (pintype "bidirectional"))
    )
    (net (code "74") (name "/FPGA_E3") (class "Default")
      (node (ref "DATA_P3") (pin "4") (pinfunction "4_4") (pintype "passive"))
      (node (ref "U1") (pin "E3") (pinfunction "IO_L54N_M3A11_3_E3") (pintype "bidirectional"))
    )
    (net (code "75") (name "/FPGA_E4") (class "Default")
      (node (ref "U1") (pin "E4") (pinfunction "IO_L54P_M3RESET_3_E4") (pintype "bidirectional"))
    )
    (net (code "76") (name "/FPGA_E6") (class "Default")
      (node (ref "U1") (pin "E6") (pinfunction "IO_L5N_0_E6") (pintype "bidirectional"))
    )
    (net (code "77") (name "/FPGA_E7") (class "Default")
      (node (ref "DATA_P4") (pin "6") (pinfunction "6_6") (pintype "passive"))
      (node (ref "U1") (pin "E7") (pinfunction "IO_L36P_GCLK15_0_E7") (pintype "bidirectional"))
    )
    (net (code "78") (name "/FPGA_E8") (class "Default")
      (node (ref "DATA_P4") (pin "3") (pinfunction "3_3") (pintype "passive"))
      (node (ref "U1") (pin "E8") (pinfunction "IO_L36N_GCLK14_0_E8") (pintype "bidirectional"))
    )
    (net (code "79") (name "/FPGA_E10") (class "Default")
      (node (ref "DATA_P2") (pin "37") (pinfunction "37_37") (pintype "passive"))
      (node (ref "U1") (pin "E10") (pinfunction "IO_L37P_GCLK13_0_E10") (pintype "bidirectional"))
    )
    (net (code "80") (name "/FPGA_E11") (class "Default")
      (node (ref "DATA_P1") (pin "37") (pinfunction "37_37") (pintype "passive"))
      (node (ref "U1") (pin "E11") (pinfunction "IO_L64N_SCP4_0_E11") (pintype "bidirectional"))
    )
    (net (code "81") (name "/FPGA_E12") (class "Default")
      (node (ref "DATA_P1") (pin "39") (pinfunction "39_39") (pintype "passive"))
      (node (ref "U1") (pin "E12") (pinfunction "IO_L1N_A24_VREF_1_E12") (pintype "bidirectional"))
    )
    (net (code "82") (name "/FPGA_E13") (class "Default")
      (node (ref "DATA_P1") (pin "23") (pinfunction "23_23") (pintype "passive"))
      (node (ref "U1") (pin "E13") (pinfunction "IO_L1P_A25_1_E13") (pintype "bidirectional"))
    )
    (net (code "83") (name "/FPGA_E15") (class "Default")
      (node (ref "DATA_P2") (pin "28") (pinfunction "28_28") (pintype "passive"))
      (node (ref "U1") (pin "E15") (pinfunction "IO_L34P_A13_M1WE_1_E15") (pintype "bidirectional"))
    )
    (net (code "84") (name "/FPGA_E16") (class "Default")
      (node (ref "DATA_P2") (pin "27") (pinfunction "27_27") (pintype "passive"))
      (node (ref "U1") (pin "E16") (pinfunction "IO_L34N_A12_M1BA2_1_E16") (pintype "bidirectional"))
    )
    (net (code "85") (name "/FPGA_F1") (class "Default")
      (node (ref "DATA_P3") (pin "9") (pinfunction "9_9") (pintype "passive"))
      (node (ref "U1") (pin "F1") (pinfunction "IO_L41N_GCLK26_M3DQ5_3_F1") (pintype "bidirectional"))
    )
    (net (code "86") (name "/FPGA_F2") (class "Default")
      (node (ref "DATA_P3") (pin "8") (pinfunction "8_8") (pintype "passive"))
      (node (ref "U1") (pin "F2") (pinfunction "IO_L41P_GCLK27_M3DQ4_3_F2") (pintype "bidirectional"))
    )
    (net (code "87") (name "/FPGA_F3") (class "Default")
      (node (ref "DATA_P3") (pin "7") (pinfunction "7_7") (pintype "passive"))
      (node (ref "U1") (pin "F3") (pinfunction "IO_L53N_M3A12_3_F3") (pintype "bidirectional"))
    )
    (net (code "88") (name "/FPGA_F4") (class "Default")
      (node (ref "DATA_P4") (pin "12") (pinfunction "12_12") (pintype "passive"))
      (node (ref "U1") (pin "F4") (pinfunction "IO_L53P_M3CKE_3_F4") (pintype "bidirectional"))
    )
    (net (code "89") (name "/FPGA_F5") (class "Default")
      (node (ref "DATA_P4") (pin "10") (pinfunction "10_10") (pintype "passive"))
      (node (ref "U1") (pin "F5") (pinfunction "IO_L55N_M3A14_3_F5") (pintype "bidirectional"))
    )
    (net (code "90") (name "/FPGA_F6") (class "Default")
      (node (ref "DATA_P4") (pin "8") (pinfunction "8_8") (pintype "passive"))
      (node (ref "U1") (pin "F6") (pinfunction "IO_L55P_M3A13_3_F6") (pintype "bidirectional"))
    )
    (net (code "91") (name "/FPGA_F7") (class "Default")
      (node (ref "DATA_P4") (pin "4") (pinfunction "4_4") (pintype "passive"))
      (node (ref "U1") (pin "F7") (pinfunction "IO_L5P_0_F7") (pintype "bidirectional"))
    )
    (net (code "92") (name "/FPGA_F9") (class "Default")
      (node (ref "DATA_P2") (pin "38") (pinfunction "38_38") (pintype "passive"))
      (node (ref "U1") (pin "F9") (pinfunction "IO_L40P_0_F9") (pintype "bidirectional"))
    )
    (net (code "93") (name "/FPGA_F10") (class "Default")
      (node (ref "DATA_P2") (pin "39") (pinfunction "39_39") (pintype "passive"))
      (node (ref "U1") (pin "F10") (pinfunction "IO_L64P_SCP5_0_F10") (pintype "bidirectional"))
    )
    (net (code "94") (name "/FPGA_F12") (class "Default")
      (node (ref "P2") (pin "6") (pinfunction "6_6") (pintype "passive"))
      (node (ref "U1") (pin "F12") (pinfunction "IO_L30P_A21_M1RESET_1_F12") (pintype "bidirectional"))
    )
    (net (code "95") (name "/FPGA_F13") (class "Default")
      (node (ref "DATA_P1") (pin "25") (pinfunction "25_25") (pintype "passive"))
      (node (ref "U1") (pin "F13") (pinfunction "IO_L32P_A17_M1A8_1_F13") (pintype "bidirectional"))
    )
    (net (code "96") (name "/FPGA_F14") (class "Default")
      (node (ref "DATA_P2") (pin "29") (pinfunction "29_29") (pintype "passive"))
      (node (ref "U1") (pin "F14") (pinfunction "IO_L32N_A16_M1A9_1_F14") (pintype "bidirectional"))
    )
    (net (code "97") (name "/FPGA_F15") (class "Default")
      (node (ref "DATA_P1") (pin "27") (pinfunction "27_27") (pintype "passive"))
      (node (ref "U1") (pin "F15") (pinfunction "IO_L35P_A11_M1A7_1_F15") (pintype "bidirectional"))
    )
    (net (code "98") (name "/FPGA_F16") (class "Default")
      (node (ref "DATA_P1") (pin "28") (pinfunction "28_28") (pintype "passive"))
      (node (ref "U1") (pin "F16") (pinfunction "IO_L35N_A10_M1A2_1_F16") (pintype "bidirectional"))
    )
    (net (code "99") (name "/FPGA_G1") (class "Default")
      (node (ref "DATA_P3") (pin "10") (pinfunction "10_10") (pintype "passive"))
      (node (ref "U1") (pin "G1") (pinfunction "IO_L40N_M3DQ7_3_G1") (pintype "bidirectional"))
    )
    (net (code "100") (name "/FPGA_G3") (class "Default")
      (node (ref "DATA_P4") (pin "13") (pinfunction "13_13") (pintype "passive"))
      (node (ref "U1") (pin "G3") (pinfunction "IO_L40P_M3DQ6_3_G3") (pintype "bidirectional"))
    )
    (net (code "101") (name "/FPGA_G5") (class "Default")
      (node (ref "DATA_P4") (pin "11") (pinfunction "11_11") (pintype "passive"))
      (node (ref "U1") (pin "G5") (pinfunction "IO_L51N_M3A4_3_G5") (pintype "bidirectional"))
    )
    (net (code "102") (name "/FPGA_G6") (class "Default")
      (node (ref "DATA_P4") (pin "9") (pinfunction "9_9") (pintype "passive"))
      (node (ref "U1") (pin "G6") (pinfunction "IO_L51P_M3A10_3_G6") (pintype "bidirectional"))
    )
    (net (code "103") (name "/FPGA_G11") (class "Default")
      (node (ref "P2") (pin "5") (pinfunction "5_5") (pintype "passive"))
      (node (ref "U1") (pin "G11") (pinfunction "IO_L30N_A20_M1A11_1_G11") (pintype "bidirectional"))
    )
    (net (code "104") (name "/FPGA_G12") (class "Default")
      (node (ref "P2") (pin "4") (pinfunction "4_4") (pintype "passive"))
      (node (ref "U1") (pin "G12") (pinfunction "IO_L38P_A5_M1CLK_1_G12") (pintype "bidirectional"))
    )
    (net (code "105") (name "/FPGA_G14") (class "Default")
      (node (ref "DATA_P2") (pin "31") (pinfunction "31_31") (pintype "passive"))
      (node (ref "U1") (pin "G14") (pinfunction "IO_L36P_A9_M1BA0_1_G14") (pintype "bidirectional"))
    )
    (net (code "106") (name "/FPGA_G16") (class "Default")
      (node (ref "DATA_P2") (pin "32") (pinfunction "32_32") (pintype "passive"))
      (node (ref "U1") (pin "G16") (pinfunction "IO_L36N_A8_M1BA1_1_G16") (pintype "bidirectional"))
    )
    (net (code "107") (name "/FPGA_H1") (class "Default")
      (node (ref "DATA_P3") (pin "13") (pinfunction "13_13") (pintype "passive"))
      (node (ref "U1") (pin "H1") (pinfunction "IO_L39N_M3LDQSN_3_H1") (pintype "bidirectional"))
    )
    (net (code "108") (name "/FPGA_H2") (class "Default")
      (node (ref "DATA_P3") (pin "12") (pinfunction "12_12") (pintype "passive"))
      (node (ref "U1") (pin "H2") (pinfunction "IO_L39P_M3LDQS_3_H2") (pintype "bidirectional"))
    )
    (net (code "109") (name "/FPGA_H3") (class "Default")
      (node (ref "DATA_P3") (pin "11") (pinfunction "11_11") (pintype "passive"))
      (node (ref "U1") (pin "H3") (pinfunction "IO_L44N_GCLK20_M3A6_3_H3") (pintype "bidirectional"))
    )
    (net (code "110") (name "/FPGA_H4") (class "Default")
      (node (ref "DATA_P4") (pin "15") (pinfunction "15_15") (pintype "passive"))
      (node (ref "U1") (pin "H4") (pinfunction "IO_L44P_GCLK21_M3A5_3_H4") (pintype "bidirectional"))
    )
    (net (code "111") (name "/FPGA_H5") (class "Default")
      (node (ref "DATA_P4") (pin "14") (pinfunction "14_14") (pintype "passive"))
      (node (ref "U1") (pin "H5") (pinfunction "IO_L43N_GCLK22_IRDY2_M3CASN_3_H5") (pintype "bidirectional"))
    )
    (net (code "112") (name "/FPGA_H11") (class "Default")
      (node (ref "P2") (pin "3") (pinfunction "3_3") (pintype "passive"))
      (node (ref "U1") (pin "H11") (pinfunction "IO_L38N_A4_M1CLKN_1_H11") (pintype "bidirectional"))
    )
    (net (code "113") (name "/FPGA_H13") (class "Default")
      (node (ref "DATA_P1") (pin "31") (pinfunction "31_31") (pintype "passive"))
      (node (ref "U1") (pin "H13") (pinfunction "IO_L39P_M1A3_1_H13") (pintype "bidirectional"))
    )
    (net (code "114") (name "/FPGA_H14") (class "Default")
      (node (ref "DATA_P1") (pin "32") (pinfunction "32_32") (pintype "passive"))
      (node (ref "U1") (pin "H14") (pinfunction "IO_L39N_M1ODT_1_H14") (pintype "bidirectional"))
    )
    (net (code "115") (name "/FPGA_H15") (class "Default")
      (node (ref "DATA_P1") (pin "29") (pinfunction "29_29") (pintype "passive"))
      (node (ref "U1") (pin "H15") (pinfunction "IO_L37P_A7_M1A0_1_H15") (pintype "bidirectional"))
    )
    (net (code "116") (name "/FPGA_H16") (class "Default")
      (node (ref "DATA_P2") (pin "34") (pinfunction "34_34") (pintype "passive"))
      (node (ref "U1") (pin "H16") (pinfunction "IO_L37N_A6_M1A1_1_H16") (pintype "bidirectional"))
    )
    (net (code "117") (name "/FPGA_J1") (class "Default")
      (node (ref "DATA_P3") (pin "16") (pinfunction "16_16") (pintype "passive"))
      (node (ref "U1") (pin "J1") (pinfunction "IO_L38N_M3DQ3_3_J1") (pintype "bidirectional"))
    )
    (net (code "118") (name "/FPGA_J3") (class "Default")
      (node (ref "DATA_P3") (pin "15") (pinfunction "15_15") (pintype "passive"))
      (node (ref "U1") (pin "J3") (pinfunction "IO_L38P_M3DQ2_3_J3") (pintype "bidirectional"))
    )
    (net (code "119") (name "/FPGA_J4") (class "Default")
      (node (ref "DATA_P3") (pin "14") (pinfunction "14_14") (pintype "passive"))
      (node (ref "U1") (pin "J4") (pinfunction "IO_L42N_GCLK24_M3LDM_3_J4") (pintype "bidirectional"))
    )
    (net (code "120") (name "/FPGA_J6") (class "Default")
      (node (ref "DATA_P4") (pin "16") (pinfunction "16_16") (pintype "passive"))
      (node (ref "U1") (pin "J6") (pinfunction "IO_L43P_GCLK23_M3RASN_3_J6") (pintype "bidirectional"))
    )
    (net (code "121") (name "/FPGA_J16") (class "Default")
      (node (ref "DATA_P2") (pin "33") (pinfunction "33_33") (pintype "passive"))
      (node (ref "U1") (pin "J16") (pinfunction "IO_L43N_GCLK4_M1DQ5_1_J16") (pintype "bidirectional"))
    )
    (net (code "122") (name "/FPGA_K1") (class "Default")
      (node (ref "DATA_P3") (pin "17") (pinfunction "17_17") (pintype "passive"))
      (node (ref "U1") (pin "K1") (pinfunction "IO_L37N_M3DQ1_3_K1") (pintype "bidirectional"))
    )
    (net (code "123") (name "/FPGA_K2") (class "Default")
      (node (ref "DATA_P3") (pin "18") (pinfunction "18_18") (pintype "passive"))
      (node (ref "U1") (pin "K2") (pinfunction "IO_L37P_M3DQ0_3_K2") (pintype "bidirectional"))
    )
    (net (code "124") (name "/FPGA_K3") (class "Default")
      (node (ref "DATA_P4") (pin "21") (pinfunction "21_21") (pintype "passive"))
      (node (ref "U1") (pin "K3") (pinfunction "IO_L42P_GCLK25_TRDY2_M3UDM_3_K3") (pintype "bidirectional"))
    )
    (net (code "125") (name "/FPGA_K5") (class "Default")
      (node (ref "DATA_P4") (pin "20") (pinfunction "20_20") (pintype "passive"))
      (node (ref "U1") (pin "K5") (pinfunction "IO_L47P_M3A0_3_K5") (pintype "bidirectional"))
    )
    (net (code "126") (name "/FPGA_K6") (class "Default")
      (node (ref "DATA_P4") (pin "17") (pinfunction "17_17") (pintype "passive"))
      (node (ref "U1") (pin "K6") (pinfunction "IO_L47N_M3A1_3_K6") (pintype "bidirectional"))
    )
    (net (code "127") (name "/FPGA_K11") (class "Default")
      (node (ref "U1") (pin "K11") (pinfunction "IO_L42N_GCLK6_TRDY1_M1LDM_1_K11") (pintype "bidirectional"))
    )
    (net (code "128") (name "/FPGA_K14") (class "Default")
      (node (ref "U1") (pin "K14") (pinfunction "IO_L41N_GCLK8_M1CASN_1_K14") (pintype "bidirectional"))
    )
    (net (code "129") (name "/FPGA_K15") (class "Default")
      (node (ref "DATA_P1") (pin "33") (pinfunction "33_33") (pintype "passive"))
      (node (ref "U1") (pin "K15") (pinfunction "IO_L44P_A3_M1DQ6_1_K15") (pintype "bidirectional"))
    )
    (net (code "130") (name "/FPGA_K16") (class "Default")
      (node (ref "DATA_P1") (pin "34") (pinfunction "34_34") (pintype "passive"))
      (node (ref "U1") (pin "K16") (pinfunction "IO_L44N_A2_M1DQ7_1_K16") (pintype "bidirectional"))
    )
    (net (code "131") (name "/FPGA_L1") (class "Default")
      (node (ref "DATA_P3") (pin "20") (pinfunction "20_20") (pintype "passive"))
      (node (ref "U1") (pin "L1") (pinfunction "IO_L36N_M3DQ9_3_L1") (pintype "bidirectional"))
    )
    (net (code "132") (name "/FPGA_L3") (class "Default")
      (node (ref "DATA_P4") (pin "25") (pinfunction "25_25") (pintype "passive"))
      (node (ref "U1") (pin "L3") (pinfunction "IO_L36P_M3DQ8_3_L3") (pintype "bidirectional"))
    )
    (net (code "133") (name "/FPGA_L4") (class "Default")
      (node (ref "DATA_P4") (pin "23") (pinfunction "23_23") (pintype "passive"))
      (node (ref "U1") (pin "L4") (pinfunction "IO_L45P_M3A3_3_L4") (pintype "bidirectional"))
    )
    (net (code "134") (name "/FPGA_L5") (class "Default")
      (node (ref "DATA_P4") (pin "18") (pinfunction "18_18") (pintype "passive"))
      (node (ref "U1") (pin "L5") (pinfunction "IO_L45N_M3ODT_3_L5") (pintype "bidirectional"))
    )
    (net (code "135") (name "/FPGA_L7") (class "Default")
      (node (ref "DATA_P4") (pin "32") (pinfunction "32_32") (pintype "passive"))
      (node (ref "U1") (pin "L7") (pinfunction "IO_L62N_D6_2_L7") (pintype "bidirectional"))
    )
    (net (code "136") (name "/FPGA_L8") (class "Default")
      (node (ref "R64") (pin "2") (pinfunction "2_2") (pintype "passive"))
      (node (ref "U1") (pin "L8") (pinfunction "IO_L62P_D5_2_L8") (pintype "bidirectional"))
    )
    (net (code "137") (name "/FPGA_L10") (class "Default")
      (node (ref "R62") (pin "2") (pinfunction "2_2") (pintype "passive"))
      (node (ref "U1") (pin "L10") (pinfunction "IO_L16P_2_L10") (pintype "bidirectional"))
    )
    (net (code "138") (name "/FPGA_L12") (class "Default")
      (node (ref "P4") (pin "2") (pinfunction "2_2") (pintype "passive"))
      (node (ref "R52") (pin "2") (pinfunction "2_2") (pintype "passive"))
      (node (ref "U1") (pin "L12") (pinfunction "IO_L53P_1_L12") (pintype "bidirectional"))
    )
    (net (code "139") (name "/FPGA_L13") (class "Default")
      (node (ref "DATA_P1") (pin "35") (pinfunction "35_35") (pintype "passive"))
      (node (ref "U1") (pin "L13") (pinfunction "IO_L53N_VREF_1_L13") (pintype "bidirectional"))
    )
    (net (code "140") (name "/FPGA_L14") (class "Default")
      (node (ref "DATA_P1") (pin "36") (pinfunction "36_36") (pintype "passive"))
      (node (ref "U1") (pin "L14") (pinfunction "IO_L47P_FWE_B_M1DQ0_1_L14") (pintype "bidirectional"))
    )
    (net (code "141") (name "/FPGA_L16") (class "Default")
      (node (ref "DATA_P2") (pin "36") (pinfunction "36_36") (pintype "passive"))
      (node (ref "U1") (pin "L16") (pinfunction "IO_L47N_LDC_M1DQ1_1_L16") (pintype "bidirectional"))
    )
    (net (code "142") (name "/FPGA_M1") (class "Default")
      (node (ref "DATA_P3") (pin "25") (pinfunction "25_25") (pintype "passive"))
      (node (ref "U1") (pin "M1") (pinfunction "IO_L35N_M3DQ11_3_M1") (pintype "bidirectional"))
    )
    (net (code "143") (name "/FPGA_M2") (class "Default")
      (node (ref "DATA_P3") (pin "23") (pinfunction "23_23") (pintype "passive"))
      (node (ref "U1") (pin "M2") (pinfunction "IO_L35P_M3DQ10_3_M2") (pintype "bidirectional"))
    )
    (net (code "144") (name "/FPGA_M3") (class "Default")
      (node (ref "DATA_P3") (pin "21") (pinfunction "21_21") (pintype "passive"))
      (node (ref "U1") (pin "M3") (pinfunction "IO_L1N_VREF_3_M3") (pintype "bidirectional"))
    )
    (net (code "145") (name "/FPGA_M4") (class "Default")
      (node (ref "U1") (pin "M4") (pinfunction "IO_L1P_3_M4") (pintype "bidirectional"))
    )
    (net (code "146") (name "/FPGA_M5") (class "Default")
      (node (ref "DATA_P4") (pin "28") (pinfunction "28_28") (pintype "passive"))
      (node (ref "U1") (pin "M5") (pinfunction "IO_L2P_3_M5") (pintype "bidirectional"))
    )
    (net (code "147") (name "/FPGA_M6") (class "Default")
      (node (ref "DATA_P4") (pin "29") (pinfunction "29_29") (pintype "passive"))
      (node (ref "U1") (pin "M6") (pinfunction "IO_L64P_D8_2_M6") (pintype "bidirectional"))
    )
    (net (code "148") (name "/FPGA_M7") (class "Default")
      (node (ref "DATA_P4") (pin "27") (pinfunction "27_27") (pintype "passive"))
      (node (ref "U1") (pin "M7") (pinfunction "IO_L31N_GCLK30_D15_2_M7") (pintype "bidirectional"))
    )
    (net (code "149") (name "/FPGA_M9") (class "Default")
      (node (ref "DATA_P4") (pin "33") (pinfunction "33_33") (pintype "passive"))
      (node (ref "U1") (pin "M9") (pinfunction "IO_L29P_GCLK3_2_M9") (pintype "bidirectional"))
    )
    (net (code "150") (name "/FPGA_M10") (class "Default")
      (node (ref "R63") (pin "2") (pinfunction "2_2") (pintype "passive"))
      (node (ref "U1") (pin "M10") (pinfunction "IO_L16N_VREF_2_M10") (pintype "bidirectional"))
    )
    (net (code "151") (name "/FPGA_M11") (class "Default")
      (node (ref "P3") (pin "2") (pinfunction "2_2") (pintype "passive"))
      (node (ref "R51") (pin "2") (pinfunction "2_2") (pintype "passive"))
      (node (ref "U1") (pin "M11") (pinfunction "IO_L2N_CMPMOSI_2_M11") (pintype "bidirectional"))
    )
    (net (code "152") (name "/FPGA_M12") (class "Default")
      (node (ref "R12") (pin "1") (pinfunction "1_1") (pintype "passive"))
      (node (ref "R15") (pin "1") (pinfunction "1_1") (pintype "passive"))
      (node (ref "U1") (pin "M12") (pinfunction "IO_L2P_CMPCLK_2_M12") (pintype "bidirectional"))
    )
    (net (code "153") (name "/FPGA_M13") (class "Default")
      (node (ref "R10") (pin "2") (pinfunction "2_2") (pintype "passive"))
      (node (ref "R9") (pin "1") (pinfunction "1_1") (pintype "passive"))
      (node (ref "U1") (pin "M13") (pinfunction "IO_L74P_AWAKE_1_M13") (pintype "bidirectional"))
    )
    (net (code "154") (name "/FPGA_M14") (class "Default")
      (node (ref "R54") (pin "2") (pinfunction "2_2") (pintype "passive"))
      (node (ref "U1") (pin "M14") (pinfunction "IO_L74N_DOUT_BUSY_1_M14") (pintype "bidirectional"))
      (node (ref "U7") (pin "2") (pinfunction "DQ_2") (pintype "passive"))
    )
    (net (code "155") (name "/FPGA_M15") (class "Default")
      (node (ref "DATA_P1") (pin "38") (pinfunction "38_38") (pintype "passive"))
      (node (ref "U1") (pin "M15") (pinfunction "IO_L46P_FCS_B_M1DQ2_1_M15") (pintype "bidirectional"))
    )
    (net (code "156") (name "/FPGA_M16") (class "Default")
      (node (ref "DATA_P2") (pin "35") (pinfunction "35_35") (pintype "passive"))
      (node (ref "U1") (pin "M16") (pinfunction "IO_L46N_FOE_B_M1DQ3_1_M16") (pintype "bidirectional"))
    )
    (net (code "157") (name "/FPGA_N1") (class "Default")
      (node (ref "DATA_P3") (pin "29") (pinfunction "29_29") (pintype "passive"))
      (node (ref "U1") (pin "N1") (pinfunction "IO_L34N_M3UDQSN_3_N1") (pintype "bidirectional"))
    )
    (net (code "158") (name "/FPGA_N3") (class "Default")
      (node (ref "DATA_P4") (pin "34") (pinfunction "34_34") (pintype "passive"))
      (node (ref "U1") (pin "N3") (pinfunction "IO_L34P_M3UDQS_3_N3") (pintype "bidirectional"))
    )
    (net (code "159") (name "/FPGA_N4") (class "Default")
      (node (ref "DATA_P3") (pin "28") (pinfunction "28_28") (pintype "passive"))
      (node (ref "U1") (pin "N4") (pinfunction "IO_L2N_3_N4") (pintype "bidirectional"))
    )
    (net (code "160") (name "/FPGA_N5") (class "Default")
      (node (ref "DATA_P3") (pin "27") (pinfunction "27_27") (pintype "passive"))
      (node (ref "U1") (pin "N5") (pinfunction "IO_L49P_D3_2_N5") (pintype "bidirectional"))
    )
    (net (code "161") (name "/FPGA_N6") (class "Default")
      (node (ref "DATA_P4") (pin "31") (pinfunction "31_31") (pintype "passive"))
      (node (ref "U1") (pin "N6") (pinfunction "IO_L64N_D9_2_N6") (pintype "bidirectional"))
    )
    (net (code "162") (name "/FPGA_N8") (class "Default")
      (node (ref "U1") (pin "N8") (pinfunction "IO_L29N_GCLK2_2_N8") (pintype "bidirectional"))
      (node (ref "U5") (pin "9") (pinfunction "CBUS4_9") (pintype "bidirectional"))
    )
    (net (code "163") (name "/FPGA_N9") (class "Default")
      (node (ref "R21") (pin "1") (pinfunction "1_1") (pintype "passive"))
      (node (ref "R22") (pin "2") (pinfunction "2_2") (pintype "passive"))
      (node (ref "U1") (pin "N9") (pinfunction "IO_L14P_D11_2_N9") (pintype "bidirectional"))
    )
    (net (code "164") (name "/FPGA_N14") (class "Default")
      (node (ref "U1") (pin "N14") (pinfunction "IO_L45P_A1_M1LDQS_1_N14") (pintype "bidirectional"))
      (node (ref "U5") (pin "22") (pinfunction "CBUS0_22") (pintype "bidirectional"))
    )
    (net (code "165") (name "/FPGA_P1") (class "Default")
      (node (ref "DATA_P3") (pin "31") (pinfunction "31_31") (pintype "passive"))
      (node (ref "U1") (pin "P1") (pinfunction "IO_L33N_M3DQ13_3_P1") (pintype "bidirectional"))
    )
    (net (code "166") (name "/FPGA_P2") (class "Default")
      (node (ref "DATA_P3") (pin "32") (pinfunction "32_32") (pintype "passive"))
      (node (ref "U1") (pin "P2") (pinfunction "IO_L33P_M3DQ12_3_P2") (pintype "bidirectional"))
    )
    (net (code "167") (name "/FPGA_P4") (class "Default")
      (node (ref "DATA_P3") (pin "35") (pinfunction "35_35") (pintype "passive"))
      (node (ref "U1") (pin "P4") (pinfunction "IO_L63P_2_P4") (pintype "bidirectional"))
    )
    (net (code "168") (name "/FPGA_P5") (class "Default")
      (node (ref "DATA_P3") (pin "38") (pinfunction "38_38") (pintype "passive"))
      (node (ref "U1") (pin "P5") (pinfunction "IO_L49N_D4_2_P5") (pintype "bidirectional"))
    )
    (net (code "169") (name "/FPGA_P6") (class "Default")
      (node (ref "DATA_P4") (pin "36") (pinfunction "36_36") (pintype "passive"))
      (node (ref "U1") (pin "P6") (pinfunction "IO_L47P_2_P6") (pintype "bidirectional"))
    )
    (net (code "170") (name "/FPGA_P7") (class "Default")
      (node (ref "DATA_P4") (pin "37") (pinfunction "37_37") (pintype "passive"))
      (node (ref "U1") (pin "P7") (pinfunction "IO_L31P_GCLK31_D14_2_P7") (pintype "bidirectional"))
    )
    (net (code "171") (name "/FPGA_P8") (class "Default")
      (node (ref "U1") (pin "P8") (pinfunction "IO_L30P_GCLK1_D13_2_P8") (pintype "bidirectional"))
      (node (ref "U5") (pin "10") (pinfunction "CBUS2_10") (pintype "bidirectional"))
    )
    (net (code "172") (name "/FPGA_P9") (class "Default")
      (node (ref "U1") (pin "P9") (pinfunction "IO_L14N_D12_2_P9") (pintype "bidirectional"))
      (node (ref "U5") (pin "6") (pinfunction "~{DSR}_6") (pintype "input"))
    )
    (net (code "173") (name "/FPGA_P11") (class "Default")
      (node (ref "J2") (pin "1") (pinfunction "1_1") (pintype "passive"))
      (node (ref "R65") (pin "1") (pinfunction "1_1") (pintype "passive"))
      (node (ref "U1") (pin "P11") (pinfunction "IO_L13N_D10_2_P11") (pintype "bidirectional"))
    )
    (net (code "174") (name "/FPGA_R1") (class "Default")
      (node (ref "DATA_P3") (pin "34") (pinfunction "34_34") (pintype "passive"))
      (node (ref "U1") (pin "R1") (pinfunction "IO_L32N_M3DQ15_3_R1") (pintype "bidirectional"))
    )
    (net (code "175") (name "/FPGA_R2") (class "Default")
      (node (ref "DATA_P3") (pin "33") (pinfunction "33_33") (pintype "passive"))
      (node (ref "U1") (pin "R2") (pinfunction "IO_L32P_M3DQ14_3_R2") (pintype "bidirectional"))
    )
    (net (code "176") (name "/FPGA_R5") (class "Default")
      (node (ref "DATA_P3") (pin "39") (pinfunction "39_39") (pintype "passive"))
      (node (ref "U1") (pin "R5") (pinfunction "IO_L48P_D7_2_R5") (pintype "bidirectional"))
    )
    (net (code "177") (name "/FPGA_R7") (class "Default")
      (node (ref "DATA_P4") (pin "39") (pinfunction "39_39") (pintype "passive"))
      (node (ref "U1") (pin "R7") (pinfunction "IO_L32P_GCLK29_2_R7") (pintype "bidirectional"))
    )
    (net (code "178") (name "/FPGA_R9") (class "Default")
      (node (ref "U1") (pin "R9") (pinfunction "IO_L23P_2_R9") (pintype "bidirectional"))
      (node (ref "U5") (pin "7") (pinfunction "~{DCD}_7") (pintype "input"))
    )
    (net (code "179") (name "/FPGA_R12") (class "Default")
      (node (ref "RXD") (pin "1") (pinfunction "TP_1") (pintype "passive"))
      (node (ref "U1") (pin "R12") (pinfunction "IO_L52P_M1DQ14_1_R12") (pintype "bidirectional"))
      (node (ref "U5") (pin "2") (pinfunction "RXD_2") (pintype "input"))
    )
    (net (code "180") (name "/FPGA_R14") (class "Default")
      (node (ref "TXD") (pin "1") (pinfunction "TP_1") (pintype "passive"))
      (node (ref "U1") (pin "R14") (pinfunction "IO_L50P_M1UDQS_1_R14") (pintype "bidirectional"))
      (node (ref "U5") (pin "30") (pinfunction "TXD_30") (pintype "output"))
    )
    (net (code "181") (name "/FPGA_R15") (class "Default")
      (node (ref "R31") (pin "1") (pinfunction "1_1") (pintype "passive"))
      (node (ref "U1") (pin "R15") (pinfunction "IO_L49P_M1DQ10_1_R15") (pintype "bidirectional"))
      (node (ref "U5") (pin "18") (pinfunction "~{RESET}_18") (pintype "input"))
    )
    (net (code "182") (name "/FPGA_R16") (class "Default")
      (node (ref "R3") (pin "2") (pinfunction "2_2") (pintype "passive"))
      (node (ref "U1") (pin "R16") (pinfunction "IO_L49N_M1DQ11_1_R16") (pintype "bidirectional"))
      (node (ref "U4") (pin "47") (pinfunction "VBUSM_47") (pintype "input"))
    )
    (net (code "183") (name "/FPGA_T4") (class "Default")
      (node (ref "DATA_P3") (pin "36") (pinfunction "36_36") (pintype "passive"))
      (node (ref "U1") (pin "T4") (pinfunction "IO_L63N_2_T4") (pintype "bidirectional"))
    )
    (net (code "184") (name "/FPGA_T5") (class "Default")
      (node (ref "DATA_P3") (pin "37") (pinfunction "37_37") (pintype "passive"))
      (node (ref "U1") (pin "T5") (pinfunction "IO_L48N_RDWR_B_VREF_2_T5") (pintype "bidirectional"))
    )
    (net (code "185") (name "/FPGA_T6") (class "Default")
      (node (ref "DATA_P4") (pin "35") (pinfunction "35_35") (pintype "passive"))
      (node (ref "U1") (pin "T6") (pinfunction "IO_L47N_2_T6") (pintype "bidirectional"))
    )
    (net (code "186") (name "/FPGA_T7") (class "Default")
      (node (ref "DATA_P4") (pin "38") (pinfunction "38_38") (pintype "passive"))
      (node (ref "U1") (pin "T7") (pinfunction "IO_L32N_GCLK28_2_T7") (pintype "bidirectional"))
    )
    (net (code "187") (name "/FPGA_T8") (class "Default")
      (node (ref "U1") (pin "T8") (pinfunction "IO_L30N_GCLK0_USERCCLK_2_T8") (pintype "bidirectional"))
      (node (ref "U5") (pin "11") (pinfunction "CBUS3_11") (pintype "bidirectional"))
    )
    (net (code "188") (name "/FPGA_T9") (class "Default")
      (node (ref "CTS") (pin "1") (pinfunction "TP_1") (pintype "passive"))
      (node (ref "U1") (pin "T9") (pinfunction "IO_L23N_2_T9") (pintype "bidirectional"))
      (node (ref "U5") (pin "8") (pinfunction "~{CTS}_8") (pintype "input"))
    )
    (net (code "189") (name "/FPGA_T12") (class "Default")
      (node (ref "U1") (pin "T12") (pinfunction "IO_L52N_M1DQ15_1_T12") (pintype "bidirectional"))
      (node (ref "U5") (pin "3") (pinfunction "~{RI}_3") (pintype "input"))
    )
    (net (code "190") (name "/FPGA_T13") (class "Default")
      (node (ref "RTS") (pin "1") (pinfunction "TP_1") (pintype "passive"))
      (node (ref "U1") (pin "T13") (pinfunction "IO_L51N_M1DQ13_1_T13") (pintype "bidirectional"))
      (node (ref "U5") (pin "32") (pinfunction "~{RTS}_32") (pintype "output"))
    )
    (net (code "191") (name "/FPGA_T14") (class "Default")
      (node (ref "U1") (pin "T14") (pinfunction "IO_L51P_M1DQ12_1_T14") (pintype "bidirectional"))
      (node (ref "U5") (pin "31") (pinfunction "~{DTR}_31") (pintype "output"))
    )
    (net (code "192") (name "/FPGA_T15") (class "Default")
      (node (ref "U1") (pin "T15") (pinfunction "IO_L50N_M1UDQSN_1_T15") (pintype "bidirectional"))
      (node (ref "U5") (pin "21") (pinfunction "CBUS1_21") (pintype "bidirectional"))
    )
    (net (code "193") (name "/HOLD_A") (class "Default")
      (node (ref "R47") (pin "2") (pinfunction "2_2") (pintype "passive"))
      (node (ref "RN3") (pin "4") (pinfunction "4_4") (pintype "power_in"))
      (node (ref "U6") (pin "7") (pinfunction "HOLD_(IO3)_7") (pintype "passive"))
    )
    (net (code "194") (name "/PG") (class "Default")
      (node (ref "POWER_IN1") (pin "3") (pinfunction "3_3") (pintype "passive"))
      (node (ref "R12") (pin "2") (pinfunction "2_2") (pintype "passive"))
    )
    (net (code "195") (name "/PLVCC3V3") (class "Default")
      (node (ref "C55") (pin "2") (pinfunction "2_2") (pintype "passive"))
      (node (ref "U5") (pin "16") (pinfunction "3V3OUT_16") (pintype "output"))
    )
    (net (code "196") (name "/PROG_B1") (class "Default")
      (node (ref "C64") (pin "1") (pinfunction "1_1") (pintype "passive"))
      (node (ref "PROG") (pin "2") (pinfunction "2_2") (pintype "passive"))
      (node (ref "R59") (pin "2") (pinfunction "2_2") (pintype "passive"))
      (node (ref "U1") (pin "T2") (pinfunction "PROGRAM_B_2_T2") (pintype "input"))
    )
    (net (code "197") (name "/PSON#") (class "Default")
      (node (ref "POWER_IN1") (pin "4") (pinfunction "4_4") (pintype "passive"))
      (node (ref "Q2") (pin "3") (pinfunction "C_3") (pintype "passive"))
      (node (ref "R17") (pin "1") (pinfunction "1_1") (pintype "passive"))
    )
    (net (code "198") (name "/SDI_A") (class "Default")
      (node (ref "RN3") (pin "3") (pinfunction "3_3") (pintype "power_in"))
      (node (ref "U6") (pin "5") (pinfunction "DI(IO0)_5") (pintype "passive"))
    )
    (net (code "199") (name "/SDO_A") (class "Default")
      (node (ref "RN3") (pin "1") (pinfunction "1_1") (pintype "power_in"))
      (node (ref "U6") (pin "2") (pinfunction "DO(IO1)_2") (pintype "passive"))
    )
    (net (code "200") (name "/TCK") (class "Default")
      (node (ref "RN2") (pin "4") (pinfunction "4_4") (pintype "power_in"))
      (node (ref "U1") (pin "C14") (pinfunction "TCK_C14") (pintype "input"))
    )
    (net (code "201") (name "/TDI") (class "Default")
      (node (ref "RN2") (pin "2") (pinfunction "2_2") (pintype "power_in"))
      (node (ref "U1") (pin "C12") (pinfunction "TDI_C12") (pintype "input"))
    )
    (net (code "202") (name "/TDO") (class "Default")
      (node (ref "RN2") (pin "3") (pinfunction "3_3") (pintype "power_in"))
      (node (ref "U1") (pin "E14") (pinfunction "TDO_E14") (pintype "output"))
    )
    (net (code "203") (name "/TMS") (class "Default")
      (node (ref "RN2") (pin "1") (pinfunction "1_1") (pintype "power_in"))
      (node (ref "U1") (pin "A15") (pinfunction "TMS_A15") (pintype "input"))
    )
    (net (code "204") (name "/USB_N") (class "Default")
      (node (ref "U4") (pin "21") (pinfunction "DMU_21") (pintype "bidirectional"))
      (node (ref "USB-B1") (pin "2") (pinfunction "D-_2") (pintype "input"))
    )
    (net (code "205") (name "/USB_P") (class "Default")
      (node (ref "U4") (pin "22") (pinfunction "DPU_22") (pintype "bidirectional"))
      (node (ref "USB-B1") (pin "3") (pinfunction "D+_3") (pintype "input"))
    )
    (net (code "206") (name "/VBUS2") (class "Default")
      (node (ref "C30") (pin "1") (pinfunction "1_1") (pintype "passive"))
      (node (ref "C43") (pin "1") (pinfunction "1_1") (pintype "passive"))
      (node (ref "F1") (pin "2") (pinfunction "2_2") (pintype "passive"))
      (node (ref "U4") (pin "44") (pinfunction "CSB2_44") (pintype "passive"))
      (node (ref "USB-A1") (pin "1") (pinfunction "VBUS_1") (pintype "power_in"))
    )
    (net (code "207") (name "/VDD25OUT") (class "Default")
      (node (ref "C38") (pin "2") (pinfunction "2_2") (pintype "passive"))
      (node (ref "C39") (pin "2") (pinfunction "2_2") (pintype "passive"))
      (node (ref "C40") (pin "2") (pinfunction "2_2") (pintype "passive"))
      (node (ref "C46") (pin "2") (pinfunction "2_2") (pintype "passive"))
      (node (ref "C47") (pin "2") (pinfunction "2_2") (pintype "passive"))
      (node (ref "C48") (pin "2") (pinfunction "2_2") (pintype "passive"))
      (node (ref "R11") (pin "2") (pinfunction "2_2") (pintype "passive"))
      (node (ref "U4") (pin "1") (pinfunction "VDD25OUT_1") (pintype "power_in"))
      (node (ref "U4") (pin "12") (pinfunction "VDD25_12") (pintype "power_in"))
      (node (ref "U4") (pin "24") (pinfunction "VDD25_24") (pintype "power_in"))
      (node (ref "U4") (pin "33") (pinfunction "VDD25_33") (pintype "power_in"))
    )
    (net (code "208") (name "/VREF") (class "Default")
      (node (ref "F2") (pin "1") (pinfunction "1_1") (pintype "passive"))
      (node (ref "JTAG1") (pin "1") (pinfunction "1_1") (pintype "passive"))
    )
    (net (code "209") (name "/V_USB") (class "Default")
      (node (ref "C52") (pin "1") (pinfunction "1_1") (pintype "passive"))
      (node (ref "J1") (pin "1") (pinfunction "1_1") (pintype "passive"))
      (node (ref "USB-B1") (pin "1") (pinfunction "VBUS_1") (pintype "power_in"))
    )
    (net (code "210") (name "/WP_A") (class "Default")
      (node (ref "R45") (pin "2") (pinfunction "2_2") (pintype "passive"))
      (node (ref "RN3") (pin "2") (pinfunction "2_2") (pintype "power_in"))
      (node (ref "U6") (pin "3") (pinfunction "WP_(IO2)_3") (pintype "passive"))
    )
    (net (code "211") (name "FANGND") (class "Default")
      (node (ref "C56") (pin "1") (pinfunction "1_1") (pintype "passive"))
      (node (ref "C58") (pin "1") (pinfunction "1_1") (pintype "passive"))
      (node (ref "C63") (pin "1") (pinfunction "1_1") (pintype "passive"))
      (node (ref "C66") (pin "1") (pinfunction "1_1") (pintype "passive"))
      (node (ref "FAN1") (pin "1") (pinfunction "1_1") (pintype "passive"))
      (node (ref "FAN2") (pin "1") (pinfunction "1_1") (pintype "passive"))
      (node (ref "FAN3") (pin "1") (pinfunction "1_1") (pintype "passive"))
      (node (ref "FB3") (pin "1") (pinfunction "1_1") (pintype "passive"))
      (node (ref "FB4") (pin "1") (pinfunction "1_1") (pintype "passive"))
    )
    (net (code "212") (name "GND") (class "Default")
      (node (ref "C1") (pin "2") (pinfunction "2_2") (pintype "passive"))
      (node (ref "C10") (pin "2") (pinfunction "2_2") (pintype "passive"))
      (node (ref "C11") (pin "2") (pinfunction "2_2") (pintype "passive"))
      (node (ref "C12") (pin "2") (pinfunction "2_2") (pintype "passive"))
      (node (ref "C13") (pin "2") (pinfunction "2_2") (pintype "passive"))
      (node (ref "C14") (pin "2") (pinfunction "2_2") (pintype "passive"))
      (node (ref "C15") (pin "1") (pinfunction "1_1") (pintype "passive"))
      (node (ref "C16") (pin "1") (pinfunction "1_1") (pintype "passive"))
      (node (ref "C17") (pin "1") (pinfunction "1_1") (pintype "passive"))
      (node (ref "C18") (pin "1") (pinfunction "1_1") (pintype "passive"))
      (node (ref "C19") (pin "1") (pinfunction "1_1") (pintype "passive"))
      (node (ref "C2") (pin "2") (pinfunction "2_2") (pintype "passive"))
      (node (ref "C20") (pin "1") (pinfunction "1_1") (pintype "passive"))
      (node (ref "C21") (pin "1") (pinfunction "1_1") (pintype "passive"))
      (node (ref "C22") (pin "1") (pinfunction "1_1") (pintype "passive"))
      (node (ref "C23") (pin "1") (pinfunction "1_1") (pintype "passive"))
      (node (ref "C24") (pin "1") (pinfunction "1_1") (pintype "passive"))
      (node (ref "C25") (pin "1") (pinfunction "1_1") (pintype "passive"))
      (node (ref "C26") (pin "2") (pinfunction "2_2") (pintype "passive"))
      (node (ref "C27") (pin "1") (pinfunction "1_1") (pintype "passive"))
      (node (ref "C28") (pin "1") (pinfunction "1_1") (pintype "passive"))
      (node (ref "C29") (pin "1") (pinfunction "1_1") (pintype "passive"))
      (node (ref "C3") (pin "2") (pinfunction "2_2") (pintype "passive"))
      (node (ref "C30") (pin "2") (pinfunction "2_2") (pintype "passive"))
      (node (ref "C31") (pin "1") (pinfunction "1_1") (pintype "passive"))
      (node (ref "C32") (pin "1") (pinfunction "1_1") (pintype "passive"))
      (node (ref "C33") (pin "1") (pinfunction "1_1") (pintype "passive"))
      (node (ref "C34") (pin "1") (pinfunction "1_1") (pintype "passive"))
      (node (ref "C35") (pin "1") (pinfunction "1_1") (pintype "passive"))
      (node (ref "C36") (pin "2") (pinfunction "2_2") (pintype "passive"))
      (node (ref "C37") (pin "2") (pinfunction "2_2") (pintype "passive"))
      (node (ref "C38") (pin "1") (pinfunction "1_1") (pintype "passive"))
      (node (ref "C39") (pin "1") (pinfunction "1_1") (pintype "passive"))
      (node (ref "C4") (pin "2") (pinfunction "2_2") (pintype "passive"))
      (node (ref "C40") (pin "1") (pinfunction "1_1") (pintype "passive"))
      (node (ref "C43") (pin "2") (pinfunction "2_2") (pintype "passive"))
      (node (ref "C44") (pin "2") (pinfunction "2_2") (pintype "passive"))
      (node (ref "C45") (pin "1") (pinfunction "1_1") (pintype "passive"))
      (node (ref "C46") (pin "1") (pinfunction "1_1") (pintype "passive"))
      (node (ref "C47") (pin "1") (pinfunction "1_1") (pintype "passive"))
      (node (ref "C48") (pin "1") (pinfunction "1_1") (pintype "passive"))
      (node (ref "C49") (pin "2") (pinfunction "2_2") (pintype "passive"))
      (node (ref "C5") (pin "2") (pinfunction "2_2") (pintype "passive"))
      (node (ref "C50") (pin "1") (pinfunction "1_1") (pintype "passive"))
      (node (ref "C51") (pin "1") (pinfunction "1_1") (pintype "passive"))
      (node (ref "C52") (pin "2") (pinfunction "2_2") (pintype "passive"))
      (node (ref "C53") (pin "1") (pinfunction "1_1") (pintype "passive"))
      (node (ref "C54") (pin "1") (pinfunction "1_1") (pintype "passive"))
      (node (ref "C55") (pin "1") (pinfunction "1_1") (pintype "passive"))
      (node (ref "C57") (pin "2") (pinfunction "2_2") (pintype "passive"))
      (node (ref "C59") (pin "1") (pinfunction "1_1") (pintype "passive"))
      (node (ref "C6") (pin "2") (pinfunction "2_2") (pintype "passive"))
      (node (ref "C60") (pin "2") (pinfunction "2_2") (pintype "passive"))
      (node (ref "C61") (pin "2") (pinfunction "2_2") (pintype "passive"))
      (node (ref "C62") (pin "2") (pinfunction "2_2") (pintype "passive"))
      (node (ref "C64") (pin "2") (pinfunction "2_2") (pintype "passive"))
      (node (ref "C65") (pin "2") (pinfunction "2_2") (pintype "passive"))
      (node (ref "C67") (pin "1") (pinfunction "1_1") (pintype "passive"))
      (node (ref "C68") (pin "1") (pinfunction "1_1") (pintype "passive"))
      (node (ref "C69") (pin "2") (pinfunction "2_2") (pintype "passive"))
      (node (ref "C7") (pin "2") (pinfunction "2_2") (pintype "passive"))
      (node (ref "C70") (pin "1") (pinfunction "1_1") (pintype "passive"))
      (node (ref "C8") (pin "2") (pinfunction "2_2") (pintype "passive"))
      (node (ref "C9") (pin "2") (pinfunction "2_2") (pintype "passive"))
      (node (ref "DATA_P1") (pin "19") (pinfunction "19_19") (pintype "passive"))
      (node (ref "DATA_P1") (pin "2") (pinfunction "2_2") (pintype "passive"))
      (node (ref "DATA_P1") (pin "22") (pinfunction "22_22") (pintype "passive"))
      (node (ref "DATA_P1") (pin "24") (pinfunction "24_24") (pintype "passive"))
      (node (ref "DATA_P1") (pin "26") (pinfunction "26_26") (pintype "passive"))
      (node (ref "DATA_P1") (pin "30") (pinfunction "30_30") (pintype "passive"))
      (node (ref "DATA_P1") (pin "40") (pinfunction "40_40") (pintype "passive"))
      (node (ref "DATA_P2") (pin "19") (pinfunction "19_19") (pintype "passive"))
      (node (ref "DATA_P2") (pin "2") (pinfunction "2_2") (pintype "passive"))
      (node (ref "DATA_P2") (pin "22") (pinfunction "22_22") (pintype "passive"))
      (node (ref "DATA_P2") (pin "24") (pinfunction "24_24") (pintype "passive"))
      (node (ref "DATA_P2") (pin "26") (pinfunction "26_26") (pintype "passive"))
      (node (ref "DATA_P2") (pin "30") (pinfunction "30_30") (pintype "passive"))
      (node (ref "DATA_P2") (pin "40") (pinfunction "40_40") (pintype "passive"))
      (node (ref "DATA_P3") (pin "19") (pinfunction "19_19") (pintype "passive"))
      (node (ref "DATA_P3") (pin "2") (pinfunction "2_2") (pintype "passive"))
      (node (ref "DATA_P3") (pin "22") (pinfunction "22_22") (pintype "passive"))
      (node (ref "DATA_P3") (pin "24") (pinfunction "24_24") (pintype "passive"))
      (node (ref "DATA_P3") (pin "26") (pinfunction "26_26") (pintype "passive"))
      (node (ref "DATA_P3") (pin "30") (pinfunction "30_30") (pintype "passive"))
      (node (ref "DATA_P3") (pin "40") (pinfunction "40_40") (pintype "passive"))
      (node (ref "DATA_P4") (pin "19") (pinfunction "19_19") (pintype "passive"))
      (node (ref "DATA_P4") (pin "2") (pinfunction "2_2") (pintype "passive"))
      (node (ref "DATA_P4") (pin "22") (pinfunction "22_22") (pintype "passive"))
      (node (ref "DATA_P4") (pin "24") (pinfunction "24_24") (pintype "passive"))
      (node (ref "DATA_P4") (pin "26") (pinfunction "26_26") (pintype "passive"))
      (node (ref "DATA_P4") (pin "30") (pinfunction "30_30") (pintype "passive"))
      (node (ref "DATA_P4") (pin "40") (pinfunction "40_40") (pintype "passive"))
      (node (ref "FB3") (pin "2") (pinfunction "2_2") (pintype "passive"))
      (node (ref "FB4") (pin "2") (pinfunction "2_2") (pintype "passive"))
      (node (ref "JTAG1") (pin "2") (pinfunction "2_2") (pintype "passive"))
      (node (ref "LED1") (pin "2") (pinfunction "K_2") (pintype "passive"))
      (node (ref "LED2") (pin "2") (pinfunction "K_2") (pintype "passive"))
      (node (ref "LED3") (pin "2") (pinfunction "K_2") (pintype "passive"))
      (node (ref "LED4") (pin "2") (pinfunction "K_2") (pintype "passive"))
      (node (ref "M1") (pin "0") (pinfunction "PIN_0") (pintype "power_in"))
      (node (ref "M2") (pin "0") (pinfunction "PIN_0") (pintype "power_in"))
      (node (ref "M3") (pin "0") (pinfunction "PIN_0") (pintype "power_in"))
      (node (ref "M4") (pin "0") (pinfunction "PIN_0") (pintype "power_in"))
      (node (ref "P1") (pin "2") (pinfunction "2_2") (pintype "passive"))
      (node (ref "P1") (pin "3") (pinfunction "3_3") (pintype "passive"))
      (node (ref "P2") (pin "2") (pinfunction "2_2") (pintype "passive"))
      (node (ref "P3") (pin "1") (pinfunction "1_1") (pintype "passive"))
      (node (ref "P4") (pin "1") (pinfunction "1_1") (pintype "passive"))
      (node (ref "POWER_IN1") (pin "10") (pinfunction "10_10") (pintype "passive"))
      (node (ref "POWER_IN1") (pin "5") (pinfunction "5_5") (pintype "passive"))
      (node (ref "POWER_IN1") (pin "8") (pinfunction "8_8") (pintype "passive"))
      (node (ref "POWER_IN1") (pin "9") (pinfunction "9_9") (pintype "passive"))
      (node (ref "PROG") (pin "1") (pinfunction "1_1") (pintype "passive"))
      (node (ref "Q1") (pin "2") (pinfunction "E_2") (pintype "passive"))
      (node (ref "Q2") (pin "2") (pinfunction "E_2") (pintype "passive"))
      (node (ref "R10") (pin "1") (pinfunction "1_1") (pintype "passive"))
      (node (ref "R13") (pin "2") (pinfunction "2_2") (pintype "passive"))
      (node (ref "R15") (pin "2") (pinfunction "2_2") (pintype "passive"))
      (node (ref "R22") (pin "1") (pinfunction "1_1") (pintype "passive"))
      (node (ref "R30") (pin "2") (pinfunction "2_2") (pintype "passive"))
      (node (ref "R33") (pin "1") (pinfunction "1_1") (pintype "passive"))
      (node (ref "R35") (pin "1") (pinfunction "1_1") (pintype "passive"))
      (node (ref "R36") (pin "1") (pinfunction "1_1") (pintype "passive"))
      (node (ref "R39") (pin "1") (pinfunction "1_1") (pintype "passive"))
      (node (ref "R4") (pin "2") (pinfunction "2_2") (pintype "passive"))
      (node (ref "R46") (pin "2") (pinfunction "2_2") (pintype "passive"))
      (node (ref "R5") (pin "2") (pinfunction "2_2") (pintype "passive"))
      (node (ref "R55") (pin "2") (pinfunction "2_2") (pintype "passive"))
      (node (ref "R56") (pin "2") (pinfunction "2_2") (pintype "passive"))
      (node (ref "R61") (pin "2") (pinfunction "2_2") (pintype "passive"))
      (node (ref "R66") (pin "2") (pinfunction "2_2") (pintype "passive"))
      (node (ref "U1") (pin "A1") (pinfunction "GND_A1") (pintype "power_in"))
      (node (ref "U1") (pin "A16") (pinfunction "GND_A16") (pintype "power_in"))
      (node (ref "U1") (pin "B11") (pinfunction "GND_B11") (pintype "power_in"))
      (node (ref "U1") (pin "B7") (pinfunction "GND_B7") (pintype "power_in"))
      (node (ref "U1") (pin "D13") (pinfunction "GND_D13") (pintype "power_in"))
      (node (ref "U1") (pin "D4") (pinfunction "GND_D4") (pintype "power_in"))
      (node (ref "U1") (pin "E9") (pinfunction "GND_E9") (pintype "power_in"))
      (node (ref "U1") (pin "G15") (pinfunction "GND_G15") (pintype "power_in"))
      (node (ref "U1") (pin "G2") (pinfunction "GND_G2") (pintype "power_in"))
      (node (ref "U1") (pin "G8") (pinfunction "GND_G8") (pintype "power_in"))
      (node (ref "U1") (pin "H12") (pinfunction "GND_H12") (pintype "power_in"))
      (node (ref "U1") (pin "H7") (pinfunction "GND_H7") (pintype "power_in"))
      (node (ref "U1") (pin "H9") (pinfunction "GND_H9") (pintype "power_in"))
      (node (ref "U1") (pin "J5") (pinfunction "GND_J5") (pintype "power_in"))
      (node (ref "U1") (pin "J8") (pinfunction "GND_J8") (pintype "power_in"))
      (node (ref "U1") (pin "K7") (pinfunction "GND_K7") (pintype "power_in"))
      (node (ref "U1") (pin "K9") (pinfunction "GND_K9") (pintype "power_in"))
      (node (ref "U1") (pin "L15") (pinfunction "GND_L15") (pintype "power_in"))
      (node (ref "U1") (pin "L2") (pinfunction "GND_L2") (pintype "power_in"))
      (node (ref "U1") (pin "M8") (pinfunction "GND_M8") (pintype "power_in"))
      (node (ref "U1") (pin "N13") (pinfunction "GND_N13") (pintype "power_in"))
      (node (ref "U1") (pin "P14") (pinfunction "SUSPEND_P14") (pintype "input"))
      (node (ref "U1") (pin "P3") (pinfunction "GND_P3") (pintype "power_in"))
      (node (ref "U1") (pin "R10") (pinfunction "GND_R10") (pintype "power_in"))
      (node (ref "U1") (pin "R6") (pinfunction "GND_R6") (pintype "power_in"))
      (node (ref "U1") (pin "T1") (pinfunction "GND_T1") (pintype "power_in"))
      (node (ref "U1") (pin "T16") (pinfunction "GND_T16") (pintype "power_in"))
      (node (ref "U2") (pin "1") (pinfunction "GND_1") (pintype "power_in"))
      (node (ref "U3") (pin "1") (pinfunction "GND_1") (pintype "passive"))
      (node (ref "U4") (pin "14") (pinfunction "TEST_14") (pintype "passive"))
      (node (ref "U4") (pin "2") (pinfunction "VSSREG_2") (pintype "power_in"))
      (node (ref "U4") (pin "23") (pinfunction "VSS_23") (pintype "power_in"))
      (node (ref "U4") (pin "27") (pinfunction "VSS_27") (pintype "power_in"))
      (node (ref "U4") (pin "3") (pinfunction "LED4_3") (pintype "passive"))
      (node (ref "U4") (pin "31") (pinfunction "DM3_31") (pintype "passive"))
      (node (ref "U4") (pin "32") (pinfunction "DP3_32") (pintype "passive"))
      (node (ref "U4") (pin "34") (pinfunction "DM4_34") (pintype "passive"))
      (node (ref "U4") (pin "35") (pinfunction "DP4_35") (pintype "passive"))
      (node (ref "U4") (pin "36") (pinfunction "VSS_36") (pintype "power_in"))
      (node (ref "U4") (pin "38") (pinfunction "PPB4_38") (pintype "passive"))
      (node (ref "U4") (pin "39") (pinfunction "CSB4_39") (pintype "passive"))
      (node (ref "U4") (pin "4") (pinfunction "LED3_4") (pintype "passive"))
      (node (ref "U4") (pin "40") (pinfunction "PPB3_40") (pintype "passive"))
      (node (ref "U4") (pin "41") (pinfunction "CSB3_41") (pintype "passive"))
      (node (ref "U4") (pin "42") (pinfunction "VSS_42") (pintype "power_in"))
      (node (ref "U4") (pin "5") (pinfunction "LED2_5") (pintype "passive"))
      (node (ref "U5") (pin "17") (pinfunction "GND_17") (pintype "power_in"))
      (node (ref "U5") (pin "20") (pinfunction "GND_20") (pintype "power_in"))
      (node (ref "U5") (pin "26") (pinfunction "TEST_26") (pintype "input"))
      (node (ref "U5") (pin "33") (pinfunction "GND_33") (pintype "power_in"))
      (node (ref "U5") (pin "4") (pinfunction "GND_4") (pintype "power_in"))
      (node (ref "U6") (pin "4") (pinfunction "GND_4") (pintype "passive"))
      (node (ref "U7") (pin "1") (pinfunction "GND_1") (pintype "passive"))
      (node (ref "USB-A1") (pin "4") (pinfunction "GND_4") (pintype "power_in"))
      (node (ref "USB-B1") (pin "4") (pinfunction "GND_4") (pintype "power_in"))
      (node (ref "Y1") (pin "2") (pinfunction "NC_2") (pintype "passive"))
    )
    (net (code "213") (name "Net-(C41-Pad2)") (class "Default")
      (node (ref "C41") (pin "2") (pinfunction "2_2") (pintype "passive"))
      (node (ref "C42") (pin "2") (pinfunction "2_2") (pintype "passive"))
      (node (ref "R11") (pin "1") (pinfunction "1_1") (pintype "passive"))
      (node (ref "U4") (pin "17") (pinfunction "AVDD_17") (pintype "power_in"))
      (node (ref "U4") (pin "19") (pinfunction "AVDD_19") (pintype "power_in"))
    )
    (net (code "214") (name "Net-(C57-Pad1)") (class "Default")
      (node (ref "C57") (pin "1") (pinfunction "1_1") (pintype "passive"))
      (node (ref "R27") (pin "2") (pinfunction "2_2") (pintype "passive"))
      (node (ref "R29") (pin "2") (pinfunction "2_2") (pintype "passive"))
      (node (ref "R30") (pin "1") (pinfunction "1_1") (pintype "passive"))
    )
    (net (code "215") (name "Net-(C60-Pad1)") (class "Default")
      (node (ref "C60") (pin "1") (pinfunction "1_1") (pintype "passive"))
      (node (ref "R42") (pin "2") (pinfunction "2_2") (pintype "passive"))
      (node (ref "R44") (pin "2") (pinfunction "2_2") (pintype "passive"))
      (node (ref "R46") (pin "1") (pinfunction "1_1") (pintype "passive"))
    )
    (net (code "216") (name "Net-(C65-Pad1)") (class "Default")
      (node (ref "C65") (pin "1") (pinfunction "1_1") (pintype "passive"))
      (node (ref "R57") (pin "2") (pinfunction "2_2") (pintype "passive"))
      (node (ref "R60") (pin "2") (pinfunction "2_2") (pintype "passive"))
      (node (ref "R61") (pin "1") (pinfunction "1_1") (pintype "passive"))
    )
    (net (code "217") (name "Net-(D1-A)") (class "Default")
      (node (ref "D1") (pin "1") (pinfunction "A_1") (pintype "passive"))
      (node (ref "FAN3") (pin "3") (pinfunction "3_3") (pintype "passive"))
      (node (ref "R25") (pin "2") (pinfunction "2_2") (pintype "passive"))
      (node (ref "R27") (pin "1") (pinfunction "1_1") (pintype "passive"))
    )
    (net (code "218") (name "Net-(D2-A)") (class "Default")
      (node (ref "D2") (pin "1") (pinfunction "A_1") (pintype "passive"))
      (node (ref "FAN2") (pin "3") (pinfunction "3_3") (pintype "passive"))
      (node (ref "R38") (pin "2") (pinfunction "2_2") (pintype "passive"))
      (node (ref "R42") (pin "1") (pinfunction "1_1") (pintype "passive"))
    )
    (net (code "219") (name "Net-(D3-A)") (class "Default")
      (node (ref "D3") (pin "1") (pinfunction "A_1") (pintype "passive"))
      (node (ref "FAN1") (pin "3") (pinfunction "3_3") (pintype "passive"))
      (node (ref "R50") (pin "2") (pinfunction "2_2") (pintype "passive"))
      (node (ref "R57") (pin "1") (pinfunction "1_1") (pintype "passive"))
    )
    (net (code "220") (name "Net-(DONE-K)") (class "Default")
      (node (ref "DONE") (pin "2") (pinfunction "K_2") (pintype "passive"))
      (node (ref "R55") (pin "1") (pinfunction "1_1") (pintype "passive"))
    )
    (net (code "221") (name "Net-(FAN1-Pad4)") (class "Default")
      (node (ref "FAN1") (pin "4") (pinfunction "4_4") (pintype "passive"))
      (node (ref "R53") (pin "1") (pinfunction "1_1") (pintype "passive"))
      (node (ref "R58") (pin "1") (pinfunction "1_1") (pintype "passive"))
    )
    (net (code "222") (name "Net-(FAN2-Pad4)") (class "Default")
      (node (ref "FAN2") (pin "4") (pinfunction "4_4") (pintype "passive"))
      (node (ref "R41") (pin "1") (pinfunction "1_1") (pintype "passive"))
      (node (ref "R43") (pin "1") (pinfunction "1_1") (pintype "passive"))
    )
    (net (code "223") (name "Net-(FAN3-Pad4)") (class "Default")
      (node (ref "FAN3") (pin "4") (pinfunction "4_4") (pintype "passive"))
      (node (ref "R26") (pin "1") (pinfunction "1_1") (pintype "passive"))
      (node (ref "R28") (pin "1") (pinfunction "1_1") (pintype "passive"))
    )
    (net (code "224") (name "Net-(J2-Pad2)") (class "Default")
      (node (ref "J2") (pin "2") (pinfunction "2_2") (pintype "passive"))
      (node (ref "R66") (pin "1") (pinfunction "1_1") (pintype "passive"))
    )
    (net (code "225") (name "Net-(JTAG1-Pad3)") (class "Default")
      (node (ref "JTAG1") (pin "3") (pinfunction "3_3") (pintype "passive"))
      (node (ref "RN2") (pin "5") (pinfunction "5_5") (pintype "power_in"))
    )
    (net (code "226") (name "Net-(JTAG1-Pad4)") (class "Default")
      (node (ref "JTAG1") (pin "4") (pinfunction "4_4") (pintype "passive"))
      (node (ref "RN2") (pin "6") (pinfunction "6_6") (pintype "power_in"))
    )
    (net (code "227") (name "Net-(JTAG1-Pad5)") (class "Default")
      (node (ref "JTAG1") (pin "5") (pinfunction "5_5") (pintype "passive"))
      (node (ref "RN2") (pin "7") (pinfunction "7_7") (pintype "power_in"))
    )
    (net (code "228") (name "Net-(JTAG1-Pad6)") (class "Default")
      (node (ref "JTAG1") (pin "6") (pinfunction "6_6") (pintype "passive"))
      (node (ref "RN2") (pin "8") (pinfunction "8_8") (pintype "power_in"))
    )
    (net (code "229") (name "Net-(LED1-A)") (class "Default")
      (node (ref "LED1") (pin "1") (pinfunction "A_1") (pintype "passive"))
      (node (ref "RN1") (pin "4") (pinfunction "4_4") (pintype "power_in"))
    )
    (net (code "230") (name "Net-(LED2-A)") (class "Default")
      (node (ref "LED2") (pin "1") (pinfunction "A_1") (pintype "passive"))
      (node (ref "RN1") (pin "3") (pinfunction "3_3") (pintype "power_in"))
    )
    (net (code "231") (name "Net-(LED3-A)") (class "Default")
      (node (ref "LED3") (pin "1") (pinfunction "A_1") (pintype "passive"))
      (node (ref "RN1") (pin "2") (pinfunction "2_2") (pintype "power_in"))
    )
    (net (code "232") (name "Net-(LED4-A)") (class "Default")
      (node (ref "LED4") (pin "1") (pinfunction "A_1") (pintype "passive"))
      (node (ref "RN1") (pin "1") (pinfunction "1_1") (pintype "power_in"))
    )
    (net (code "233") (name "Net-(P1-Pad4)") (class "Default")
      (node (ref "P1") (pin "4") (pinfunction "4_4") (pintype "passive"))
      (node (ref "R62") (pin "1") (pinfunction "1_1") (pintype "passive"))
    )
    (net (code "234") (name "Net-(P1-Pad5)") (class "Default")
      (node (ref "P1") (pin "5") (pinfunction "5_5") (pintype "passive"))
      (node (ref "R63") (pin "1") (pinfunction "1_1") (pintype "passive"))
    )
    (net (code "235") (name "Net-(P1-Pad6)") (class "Default")
      (node (ref "P1") (pin "6") (pinfunction "6_6") (pintype "passive"))
      (node (ref "R64") (pin "1") (pinfunction "1_1") (pintype "passive"))
    )
    (net (code "236") (name "Net-(Q1-B)") (class "Default")
      (node (ref "Q1") (pin "1") (pinfunction "B_1") (pintype "passive"))
      (node (ref "R9") (pin "2") (pinfunction "2_2") (pintype "passive"))
    )
    (net (code "237") (name "Net-(Q2-B)") (class "Default")
      (node (ref "Q2") (pin "1") (pinfunction "B_1") (pintype "passive"))
      (node (ref "R21") (pin "2") (pinfunction "2_2") (pintype "passive"))
    )
    (net (code "238") (name "Net-(R4-Pad1)") (class "Default")
      (node (ref "R4") (pin "1") (pinfunction "1_1") (pintype "passive"))
      (node (ref "USB-B1") (pin "5") (pinfunction "SHLD_5") (pintype "passive"))
      (node (ref "USB-B1") (pin "6") (pinfunction "SHLD_6") (pintype "passive"))
    )
    (net (code "239") (name "Net-(R5-Pad1)") (class "Default")
      (node (ref "R5") (pin "1") (pinfunction "1_1") (pintype "passive"))
      (node (ref "USB-A1") (pin "5") (pinfunction "SHLD_5") (pintype "passive"))
      (node (ref "USB-A1") (pin "6") (pinfunction "SHLD_6") (pintype "passive"))
    )
    (net (code "240") (name "Net-(U4-AMBER)") (class "Default")
      (node (ref "U4") (pin "7") (pinfunction "AMBER_7") (pintype "passive"))
      (node (ref "U4") (pin "8") (pinfunction "GREEN_8") (pintype "passive"))
    )
    (net (code "241") (name "Net-(U4-AVSS(R))") (class "Default")
      (node (ref "C41") (pin "1") (pinfunction "1_1") (pintype "passive"))
      (node (ref "C42") (pin "1") (pinfunction "1_1") (pintype "passive"))
      (node (ref "R13") (pin "1") (pinfunction "1_1") (pintype "passive"))
      (node (ref "R14") (pin "2") (pinfunction "2_2") (pintype "passive"))
      (node (ref "U4") (pin "16") (pinfunction "AVSS(R)_16") (pintype "power_in"))
      (node (ref "U4") (pin "18") (pinfunction "AVSS_18") (pintype "power_in"))
    )
    (net (code "242") (name "Net-(U4-CSB1)") (class "Default")
      (node (ref "R19") (pin "1") (pinfunction "1_1") (pintype "passive"))
      (node (ref "U4") (pin "46") (pinfunction "CSB1_46") (pintype "passive"))
    )
    (net (code "243") (name "Net-(U4-PPB1)") (class "Default")
      (node (ref "R18") (pin "1") (pinfunction "1_1") (pintype "passive"))
      (node (ref "U4") (pin "45") (pinfunction "PPB1_45") (pintype "passive"))
    )
    (net (code "244") (name "Net-(U4-PPB2)") (class "Default")
      (node (ref "R20") (pin "1") (pinfunction "1_1") (pintype "passive"))
      (node (ref "U4") (pin "43") (pinfunction "PPB2_43") (pintype "passive"))
    )
    (net (code "245") (name "Net-(U4-RREF)") (class "Default")
      (node (ref "R14") (pin "1") (pinfunction "1_1") (pintype "passive"))
      (node (ref "U4") (pin "15") (pinfunction "RREF_15") (pintype "passive"))
    )
    (net (code "246") (name "Net-(U4-SYSRSTB)") (class "Default")
      (node (ref "C45") (pin "2") (pinfunction "2_2") (pintype "passive"))
      (node (ref "R16") (pin "2") (pinfunction "2_2") (pintype "passive"))
      (node (ref "U4") (pin "37") (pinfunction "SYSRSTB_37") (pintype "input"))
    )
    (net (code "247") (name "Net-(U4-VDD33REG)") (class "Default")
      (node (ref "C31") (pin "2") (pinfunction "2_2") (pintype "passive"))
      (node (ref "C32") (pin "2") (pinfunction "2_2") (pintype "passive"))
      (node (ref "C33") (pin "2") (pinfunction "2_2") (pintype "passive"))
      (node (ref "C34") (pin "2") (pinfunction "2_2") (pintype "passive"))
      (node (ref "C35") (pin "2") (pinfunction "2_2") (pintype "passive"))
      (node (ref "R8") (pin "1") (pinfunction "1_1") (pintype "passive"))
      (node (ref "U4") (pin "20") (pinfunction "VDD33_20") (pintype "power_in"))
      (node (ref "U4") (pin "30") (pinfunction "VDD33_30") (pintype "power_in"))
      (node (ref "U4") (pin "48") (pinfunction "VDD33REG_48") (pintype "power_in"))
      (node (ref "U4") (pin "9") (pinfunction "VDD33_9") (pintype "power_in"))
    )
    (net (code "248") (name "Net-(U4-X1)") (class "Default")
      (node (ref "C36") (pin "1") (pinfunction "1_1") (pintype "passive"))
      (node (ref "R6") (pin "1") (pinfunction "1_1") (pintype "passive"))
      (node (ref "U4") (pin "10") (pinfunction "X1_10") (pintype "input"))
      (node (ref "Y2") (pin "2") (pinfunction "OSC2_2") (pintype "passive"))
    )
    (net (code "249") (name "Net-(U4-X2)") (class "Default")
      (node (ref "R7") (pin "1") (pinfunction "1_1") (pintype "passive"))
      (node (ref "U4") (pin "11") (pinfunction "X2_11") (pintype "output"))
    )
    (net (code "250") (name "Net-(U5-AGND)") (class "Default")
      (node (ref "R35") (pin "2") (pinfunction "2_2") (pintype "passive"))
      (node (ref "U5") (pin "24") (pinfunction "AGND_24") (pintype "power_in"))
    )
    (net (code "251") (name "Net-(U5-VCC)") (class "Default")
      (node (ref "C53") (pin "2") (pinfunction "2_2") (pintype "passive"))
      (node (ref "C67") (pin "2") (pinfunction "2_2") (pintype "passive"))
      (node (ref "R23") (pin "2") (pinfunction "2_2") (pintype "passive"))
      (node (ref "U5") (pin "19") (pinfunction "VCC_19") (pintype "power_in"))
    )
    (net (code "252") (name "Net-(U5-VCCIO)") (class "Default")
      (node (ref "C54") (pin "2") (pinfunction "2_2") (pintype "passive"))
      (node (ref "C68") (pin "2") (pinfunction "2_2") (pintype "passive"))
      (node (ref "R24") (pin "2") (pinfunction "2_2") (pintype "passive"))
      (node (ref "U5") (pin "1") (pinfunction "VCCIO_1") (pintype "power_in"))
    )
    (net (code "253") (name "Net-(Y1-OSC1)") (class "Default")
      (node (ref "C29") (pin "2") (pinfunction "2_2") (pintype "passive"))
      (node (ref "R1") (pin "1") (pinfunction "1_1") (pintype "passive"))
      (node (ref "Y1") (pin "1") (pinfunction "OSC1_1") (pintype "passive"))
      (node (ref "Y1") (pin "4") (pinfunction "NC_4") (pintype "passive"))
    )
    (net (code "254") (name "Net-(Y1-OSC2)") (class "Default")
      (node (ref "R2") (pin "2") (pinfunction "2_2") (pintype "passive"))
      (node (ref "Y1") (pin "3") (pinfunction "OSC2_3") (pintype "passive"))
    )
    (net (code "255") (name "Net-(Y2-OSC1)") (class "Default")
      (node (ref "C37") (pin "1") (pinfunction "1_1") (pintype "passive"))
      (node (ref "R6") (pin "2") (pinfunction "2_2") (pintype "passive"))
      (node (ref "R7") (pin "2") (pinfunction "2_2") (pintype "passive"))
      (node (ref "Y2") (pin "1") (pinfunction "OSC1_1") (pintype "passive"))
    )
    (net (code "256") (name "VCC1V2") (class "Default")
      (node (ref "C11") (pin "1") (pinfunction "1_1") (pintype "passive"))
      (node (ref "C12") (pin "1") (pinfunction "1_1") (pintype "passive"))
      (node (ref "C13") (pin "1") (pinfunction "1_1") (pintype "passive"))
      (node (ref "C21") (pin "2") (pinfunction "2_2") (pintype "passive"))
      (node (ref "C22") (pin "2") (pinfunction "2_2") (pintype "passive"))
      (node (ref "C23") (pin "2") (pinfunction "2_2") (pintype "passive"))
      (node (ref "C24") (pin "2") (pinfunction "2_2") (pintype "passive"))
      (node (ref "C25") (pin "2") (pinfunction "2_2") (pintype "passive"))
      (node (ref "C26") (pin "1") (pinfunction "1_1") (pintype "passive"))
      (node (ref "C27") (pin "2") (pinfunction "2_2") (pintype "passive"))
      (node (ref "U1") (pin "G7") (pinfunction "VCCINT_G7") (pintype "power_in"))
      (node (ref "U1") (pin "G9") (pinfunction "VCCINT_G9") (pintype "power_in"))
      (node (ref "U1") (pin "H10") (pinfunction "VCCINT_H10") (pintype "power_in"))
      (node (ref "U1") (pin "H8") (pinfunction "VCCINT_H8") (pintype "power_in"))
      (node (ref "U1") (pin "J7") (pinfunction "VCCINT_J7") (pintype "power_in"))
      (node (ref "U1") (pin "J9") (pinfunction "VCCINT_J9") (pintype "power_in"))
      (node (ref "U1") (pin "K10") (pinfunction "VCCINT_K10") (pintype "power_in"))
      (node (ref "U1") (pin "K8") (pinfunction "VCCINT_K8") (pintype "power_in"))
      (node (ref "U3") (pin "3") (pinfunction "VOUT_3") (pintype "passive"))
    )
    (net (code "257") (name "VCC3V3") (class "Default")
      (node (ref "C1") (pin "1") (pinfunction "1_1") (pintype "passive"))
      (node (ref "C10") (pin "1") (pinfunction "1_1") (pintype "passive"))
      (node (ref "C14") (pin "1") (pinfunction "1_1") (pintype "passive"))
      (node (ref "C16") (pin "2") (pinfunction "2_2") (pintype "passive"))
      (node (ref "C17") (pin "2") (pinfunction "2_2") (pintype "passive"))
      (node (ref "C18") (pin "2") (pinfunction "2_2") (pintype "passive"))
      (node (ref "C19") (pin "2") (pinfunction "2_2") (pintype "passive"))
      (node (ref "C2") (pin "1") (pinfunction "1_1") (pintype "passive"))
      (node (ref "C20") (pin "2") (pinfunction "2_2") (pintype "passive"))
      (node (ref "C28") (pin "2") (pinfunction "2_2") (pintype "passive"))
      (node (ref "C3") (pin "1") (pinfunction "1_1") (pintype "passive"))
      (node (ref "C4") (pin "1") (pinfunction "1_1") (pintype "passive"))
      (node (ref "C5") (pin "1") (pinfunction "1_1") (pintype "passive"))
      (node (ref "C59") (pin "2") (pinfunction "2_2") (pintype "passive"))
      (node (ref "C6") (pin "1") (pinfunction "1_1") (pintype "passive"))
      (node (ref "C61") (pin "1") (pinfunction "1_1") (pintype "passive"))
      (node (ref "C62") (pin "1") (pinfunction "1_1") (pintype "passive"))
      (node (ref "C69") (pin "1") (pinfunction "1_1") (pintype "passive"))
      (node (ref "C7") (pin "1") (pinfunction "1_1") (pintype "passive"))
      (node (ref "C70") (pin "2") (pinfunction "2_2") (pintype "passive"))
      (node (ref "C8") (pin "1") (pinfunction "1_1") (pintype "passive"))
      (node (ref "C9") (pin "1") (pinfunction "1_1") (pintype "passive"))
      (node (ref "F2") (pin "2") (pinfunction "2_2") (pintype "passive"))
      (node (ref "P1") (pin "1") (pinfunction "1_1") (pintype "passive"))
      (node (ref "P2") (pin "1") (pinfunction "1_1") (pintype "passive"))
      (node (ref "P3") (pin "3") (pinfunction "3_3") (pintype "passive"))
      (node (ref "P4") (pin "3") (pinfunction "3_3") (pintype "passive"))
      (node (ref "R1") (pin "2") (pinfunction "2_2") (pintype "passive"))
      (node (ref "R16") (pin "1") (pinfunction "1_1") (pintype "passive"))
      (node (ref "R18") (pin "2") (pinfunction "2_2") (pintype "passive"))
      (node (ref "R19") (pin "2") (pinfunction "2_2") (pintype "passive"))
      (node (ref "R20") (pin "2") (pinfunction "2_2") (pintype "passive"))
      (node (ref "R24") (pin "1") (pinfunction "1_1") (pintype "passive"))
      (node (ref "R26") (pin "2") (pinfunction "2_2") (pintype "passive"))
      (node (ref "R3") (pin "1") (pinfunction "1_1") (pintype "passive"))
      (node (ref "R31") (pin "2") (pinfunction "2_2") (pintype "passive"))
      (node (ref "R32") (pin "1") (pinfunction "1_1") (pintype "passive"))
      (node (ref "R34") (pin "1") (pinfunction "1_1") (pintype "passive"))
      (node (ref "R37") (pin "1") (pinfunction "1_1") (pintype "passive"))
      (node (ref "R40") (pin "1") (pinfunction "1_1") (pintype "passive"))
      (node (ref "R41") (pin "2") (pinfunction "2_2") (pintype "passive"))
      (node (ref "R45") (pin "1") (pinfunction "1_1") (pintype "passive"))
      (node (ref "R47") (pin "1") (pinfunction "1_1") (pintype "passive"))
      (node (ref "R48") (pin "1") (pinfunction "1_1") (pintype "passive"))
      (node (ref "R49") (pin "1") (pinfunction "1_1") (pintype "passive"))
      (node (ref "R51") (pin "1") (pinfunction "1_1") (pintype "passive"))
      (node (ref "R52") (pin "1") (pinfunction "1_1") (pintype "passive"))
      (node (ref "R53") (pin "2") (pinfunction "2_2") (pintype "passive"))
      (node (ref "R54") (pin "1") (pinfunction "1_1") (pintype "passive"))
      (node (ref "R59") (pin "1") (pinfunction "1_1") (pintype "passive"))
      (node (ref "R65") (pin "2") (pinfunction "2_2") (pintype "passive"))
      (node (ref "R8") (pin "2") (pinfunction "2_2") (pintype "passive"))
      (node (ref "U1") (pin "B13") (pinfunction "VCCO_0_B13") (pintype "power_in"))
      (node (ref "U1") (pin "B4") (pinfunction "VCCO_0_B4") (pintype "power_in"))
      (node (ref "U1") (pin "B9") (pinfunction "VCCO_0_B9") (pintype "power_in"))
      (node (ref "U1") (pin "D10") (pinfunction "VCCO_0_D10") (pintype "power_in"))
      (node (ref "U1") (pin "D15") (pinfunction "VCCO_1_D15") (pintype "power_in"))
      (node (ref "U1") (pin "D2") (pinfunction "VCCO_3_D2") (pintype "power_in"))
      (node (ref "U1") (pin "D7") (pinfunction "VCCO_0_D7") (pintype "power_in"))
      (node (ref "U1") (pin "E5") (pinfunction "VCCAUX_E5") (pintype "power_in"))
      (node (ref "U1") (pin "F11") (pinfunction "VCCAUX_F11") (pintype "power_in"))
      (node (ref "U1") (pin "F8") (pinfunction "VCCAUX_F8") (pintype "power_in"))
      (node (ref "U1") (pin "G10") (pinfunction "VCCAUX_G10") (pintype "power_in"))
      (node (ref "U1") (pin "G13") (pinfunction "VCCO_1_G13") (pintype "power_in"))
      (node (ref "U1") (pin "G4") (pinfunction "VCCO_3_G4") (pintype "power_in"))
      (node (ref "U1") (pin "H6") (pinfunction "VCCAUX_H6") (pintype "power_in"))
      (node (ref "U1") (pin "J10") (pinfunction "VCCAUX_J10") (pintype "power_in"))
      (node (ref "U1") (pin "J15") (pinfunction "VCCO_1_J15") (pintype "power_in"))
      (node (ref "U1") (pin "J2") (pinfunction "VCCO_3_J2") (pintype "power_in"))
      (node (ref "U1") (pin "K13") (pinfunction "VCCO_1_K13") (pintype "power_in"))
      (node (ref "U1") (pin "K4") (pinfunction "VCCO_3_K4") (pintype "power_in"))
      (node (ref "U1") (pin "L6") (pinfunction "VCCAUX_L6") (pintype "power_in"))
      (node (ref "U1") (pin "L9") (pinfunction "VCCAUX_L9") (pintype "power_in"))
      (node (ref "U1") (pin "N10") (pinfunction "VCCO_2_N10") (pintype "power_in"))
      (node (ref "U1") (pin "N15") (pinfunction "VCCO_1_N15") (pintype "power_in"))
      (node (ref "U1") (pin "N2") (pinfunction "VCCO_3_N2") (pintype "power_in"))
      (node (ref "U1") (pin "N7") (pinfunction "VCCO_2_N7") (pintype "power_in"))
      (node (ref "U1") (pin "R13") (pinfunction "VCCO_1_R13") (pintype "power_in"))
      (node (ref "U1") (pin "R4") (pinfunction "VCCO_2_R4") (pintype "power_in"))
      (node (ref "U1") (pin "R8") (pinfunction "VCCO_2_R8") (pintype "power_in"))
      (node (ref "U2") (pin "2") (pinfunction "OUT_2") (pintype "power_in"))
      (node (ref "U2") (pin "4") (pinfunction "TAB_4") (pintype "power_in"))
      (node (ref "U3") (pin "2") (pinfunction "VIN_2") (pintype "passive"))
      (node (ref "U4") (pin "13") (pinfunction "BUS_B_13") (pintype "input"))
      (node (ref "U4") (pin "6") (pinfunction "LED1_6") (pintype "passive"))
      (node (ref "U6") (pin "8") (pinfunction "VCC_8") (pintype "passive"))
      (node (ref "U7") (pin "3") (pinfunction "VDD_3") (pintype "passive"))
    )
    (net (code "258") (name "VCC5") (class "Default")
      (node (ref "C15") (pin "2") (pinfunction "2_2") (pintype "passive"))
      (node (ref "C44") (pin "1") (pinfunction "1_1") (pintype "passive"))
      (node (ref "F1") (pin "1") (pinfunction "1_1") (pintype "passive"))
      (node (ref "J1") (pin "2") (pinfunction "2_2") (pintype "passive"))
      (node (ref "POWER_IN1") (pin "1") (pinfunction "1_1") (pintype "passive"))
      (node (ref "POWER_IN1") (pin "6") (pinfunction "6_6") (pintype "passive"))
      (node (ref "R17") (pin "2") (pinfunction "2_2") (pintype "passive"))
      (node (ref "R23") (pin "1") (pinfunction "1_1") (pintype "passive"))
      (node (ref "U2") (pin "3") (pinfunction "IN_3") (pintype "power_in"))
    )
    (net (code "259") (name "VCC12V") (class "Default")
      (node (ref "C49") (pin "1") (pinfunction "1_1") (pintype "passive"))
      (node (ref "C50") (pin "2") (pinfunction "2_2") (pintype "passive"))
      (node (ref "C51") (pin "2") (pinfunction "2_2") (pintype "passive"))
      (node (ref "FB1") (pin "2") (pinfunction "2_2") (pintype "passive"))
      (node (ref "FB2") (pin "2") (pinfunction "2_2") (pintype "passive"))
      (node (ref "POWER_IN1") (pin "2") (pinfunction "2_2") (pintype "passive"))
      (node (ref "POWER_IN1") (pin "7") (pinfunction "7_7") (pintype "passive"))
    )
    (net (code "260") (name "VFAN12V") (class "Default")
      (node (ref "C56") (pin "2") (pinfunction "2_2") (pintype "passive"))
      (node (ref "C58") (pin "2") (pinfunction "2_2") (pintype "passive"))
      (node (ref "C63") (pin "2") (pinfunction "2_2") (pintype "passive"))
      (node (ref "C66") (pin "2") (pinfunction "2_2") (pintype "passive"))
      (node (ref "D1") (pin "2") (pinfunction "K_2") (pintype "passive"))
      (node (ref "D2") (pin "2") (pinfunction "K_2") (pintype "passive"))
      (node (ref "D3") (pin "2") (pinfunction "K_2") (pintype "passive"))
      (node (ref "FAN1") (pin "2") (pinfunction "2_2") (pintype "passive"))
      (node (ref "FAN2") (pin "2") (pinfunction "2_2") (pintype "passive"))
      (node (ref "FAN3") (pin "2") (pinfunction "2_2") (pintype "passive"))
      (node (ref "FB1") (pin "1") (pinfunction "1_1") (pintype "passive"))
      (node (ref "FB2") (pin "1") (pinfunction "1_1") (pintype "passive"))
      (node (ref "R25") (pin "1") (pinfunction "1_1") (pintype "passive"))
      (node (ref "R38") (pin "1") (pinfunction "1_1") (pintype "passive"))
      (node (ref "R50") (pin "1") (pinfunction "1_1") (pintype "passive"))
    )
    (net (code "261") (name "unconnected-(MASK1-Pad1)") (class "Default")
      (node (ref "MASK1") (pin "1") (pinfunction "1_1") (pintype "passive"))
    )
    (net (code "262") (name "unconnected-(MASK2-Pad1)") (class "Default")
      (node (ref "MASK2") (pin "1") (pinfunction "1_1") (pintype "passive"))
    )
    (net (code "263") (name "unconnected-(TPM1-MASKTEST-Pad0)") (class "Default")
      (node (ref "TPM1") (pin "0") (pinfunction "MASKTEST_0") (pintype "passive"))
    )
    (net (code "264") (name "unconnected-(TPM2-MASKTEST-Pad0)") (class "Default")
      (node (ref "TPM2") (pin "0") (pinfunction "MASKTEST_0") (pintype "passive"))
    )
    (net (code "265") (name "unconnected-(U1E-CMPCS_B_2-PadL11)") (class "Default")
      (node (ref "U1") (pin "L11") (pinfunction "CMPCS_B_2_L11") (pintype "input+no_connect"))
    )
    (net (code "266") (name "unconnected-(U5-NC-Pad5)") (class "Default")
      (node (ref "U5") (pin "5") (pinfunction "NC_5") (pintype "passive"))
    )
    (net (code "267") (name "unconnected-(U5-NC-Pad12)") (class "Default")
      (node (ref "U5") (pin "12") (pinfunction "NC_12") (pintype "passive"))
    )
    (net (code "268") (name "unconnected-(U5-NC-Pad13)") (class "Default")
      (node (ref "U5") (pin "13") (pinfunction "NC_13") (pintype "passive"))
    )
    (net (code "269") (name "unconnected-(U5-NC-Pad23)") (class "Default")
      (node (ref "U5") (pin "23") (pinfunction "NC_23") (pintype "passive"))
    )
    (net (code "270") (name "unconnected-(U5-NC-Pad25)") (class "Default")
      (node (ref "U5") (pin "25") (pinfunction "NC_25") (pintype "passive"))
    )
    (net (code "271") (name "unconnected-(U5-NC-Pad29)") (class "Default")
      (node (ref "U5") (pin "29") (pinfunction "NC_29") (pintype "passive"))
    )
    (net (code "272") (name "unconnected-(U5-OSCI-Pad27)") (class "Default")
      (node (ref "U5") (pin "27") (pinfunction "OSCI_27") (pintype "input"))
    )
    (net (code "273") (name "unconnected-(U5-OSCO-Pad28)") (class "Default")
      (node (ref "U5") (pin "28") (pinfunction "OSCO_28") (pintype "output"))
    )
  )
)
